# schematic.net
KiCad netlist of a schematic drawn in Altium Designer
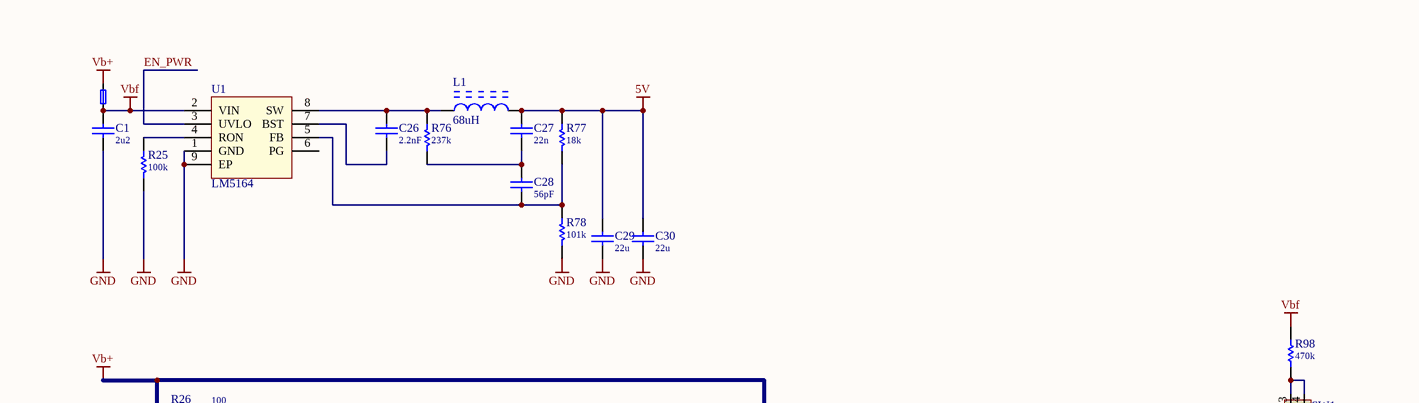
[diagram p0: schematic.SchDoc, top]
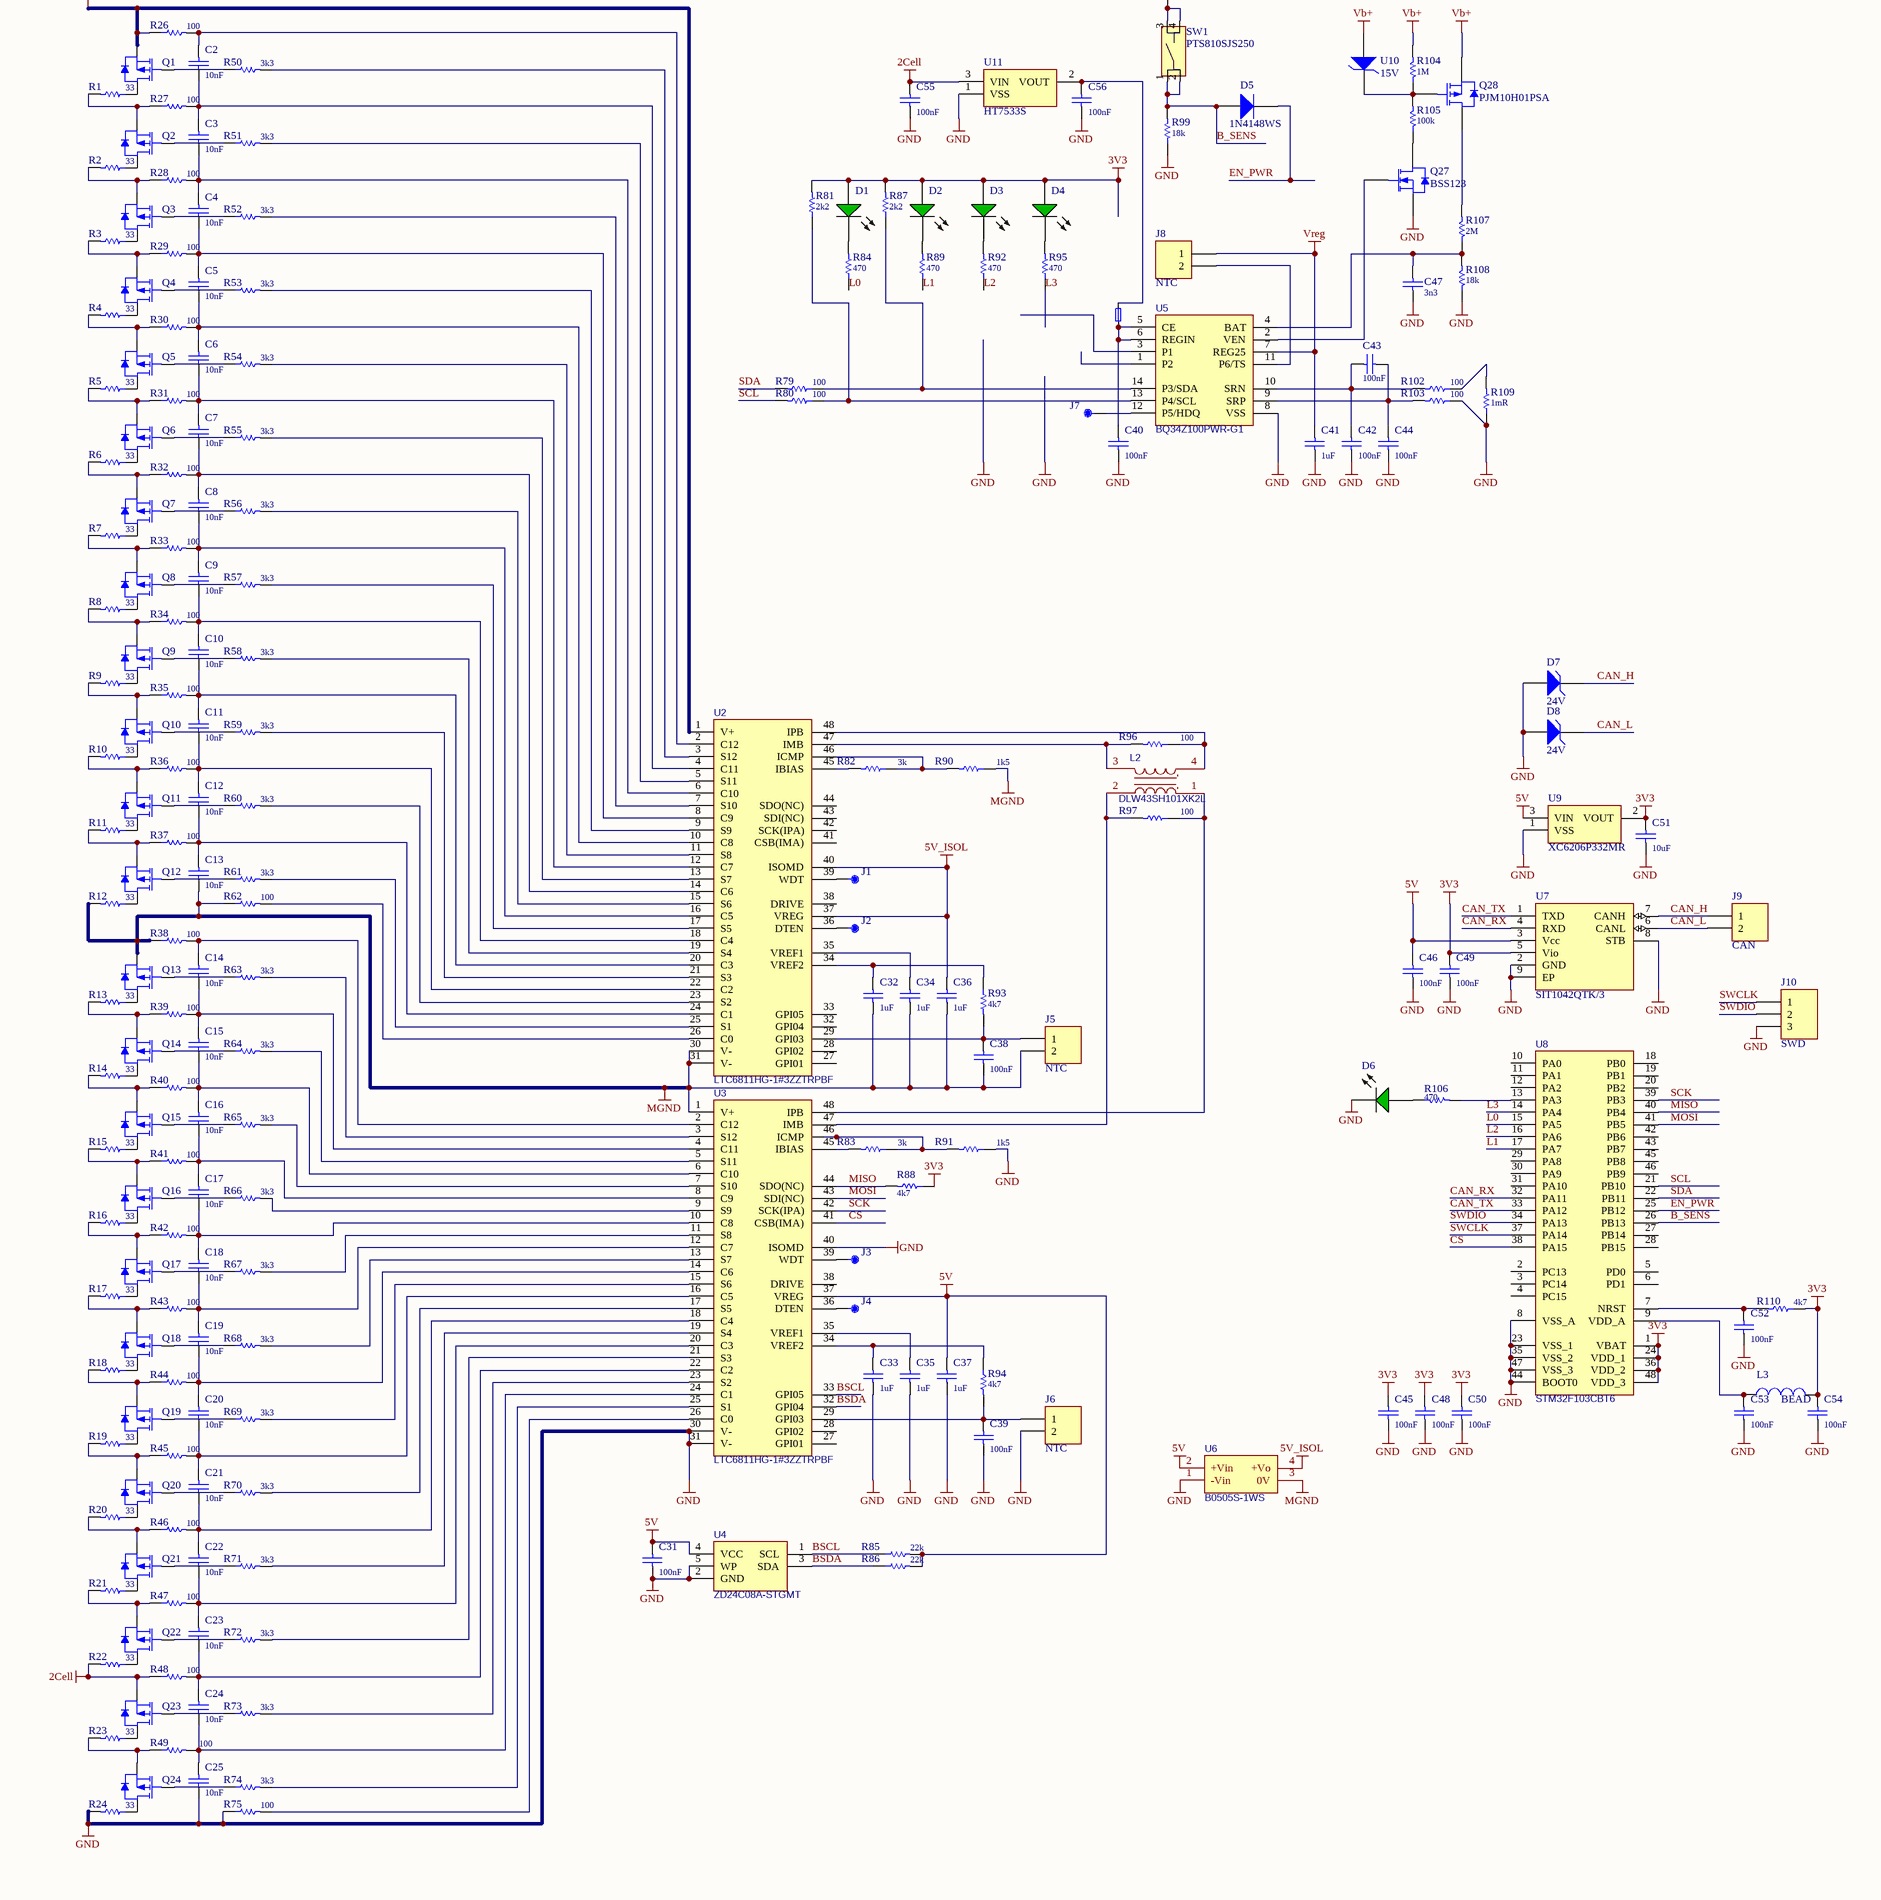
[diagram p1: schematic.SchDoc, bottom]

(export (version "E")
  (design (tool "Eeschema 10.0.6"))
  (components
    (comp (ref "C1")
      (value "2u2")
      (footprint "C1210")
      (description "2.2uF 100V 1210")
      (libsource (lib "Miscellaneous Devices") (part "CAP"))
    )
    (comp (ref "C2")
      (value "10nF")
      (footprint "C0603")
      (description "10nF 50V 0603")
      (libsource (lib "Miscellaneous Devices") (part "CAP"))
    )
    (comp (ref "C3")
      (value "10nF")
      (footprint "C0603")
      (description "10nF 50V 0603")
      (libsource (lib "Miscellaneous Devices") (part "CAP"))
    )
    (comp (ref "C4")
      (value "10nF")
      (footprint "C0603")
      (description "10nF 50V 0603")
      (libsource (lib "Miscellaneous Devices") (part "CAP"))
    )
    (comp (ref "C5")
      (value "10nF")
      (footprint "C0603")
      (description "10nF 50V 0603")
      (libsource (lib "Miscellaneous Devices") (part "CAP"))
    )
    (comp (ref "C6")
      (value "10nF")
      (footprint "C0603")
      (description "10nF 50V 0603")
      (libsource (lib "Miscellaneous Devices") (part "CAP"))
    )
    (comp (ref "C7")
      (value "10nF")
      (footprint "C0603")
      (description "10nF 50V 0603")
      (libsource (lib "Miscellaneous Devices") (part "CAP"))
    )
    (comp (ref "C8")
      (value "10nF")
      (footprint "C0603")
      (description "10nF 50V 0603")
      (libsource (lib "Miscellaneous Devices") (part "CAP"))
    )
    (comp (ref "C9")
      (value "10nF")
      (footprint "C0603")
      (description "10nF 50V 0603")
      (libsource (lib "Miscellaneous Devices") (part "CAP"))
    )
    (comp (ref "C10")
      (value "10nF")
      (footprint "C0603")
      (description "10nF 50V 0603")
      (libsource (lib "Miscellaneous Devices") (part "CAP"))
    )
    (comp (ref "C11")
      (value "10nF")
      (footprint "C0603")
      (description "10nF 50V 0603")
      (libsource (lib "Miscellaneous Devices") (part "CAP"))
    )
    (comp (ref "C12")
      (value "10nF")
      (footprint "C0603")
      (description "10nF 50V 0603")
      (libsource (lib "Miscellaneous Devices") (part "CAP"))
    )
    (comp (ref "C13")
      (value "10nF")
      (footprint "C0603")
      (description "10nF 50V 0603")
      (libsource (lib "Miscellaneous Devices") (part "CAP"))
    )
    (comp (ref "C14")
      (value "10nF")
      (footprint "C0603")
      (description "10nF 50V 0603")
      (libsource (lib "Miscellaneous Devices") (part "CAP"))
    )
    (comp (ref "C15")
      (value "10nF")
      (footprint "C0603")
      (description "10nF 50V 0603")
      (libsource (lib "Miscellaneous Devices") (part "CAP"))
    )
    (comp (ref "C16")
      (value "10nF")
      (footprint "C0603")
      (description "10nF 50V 0603")
      (libsource (lib "Miscellaneous Devices") (part "CAP"))
    )
    (comp (ref "C17")
      (value "10nF")
      (footprint "C0603")
      (description "10nF 50V 0603")
      (libsource (lib "Miscellaneous Devices") (part "CAP"))
    )
    (comp (ref "C18")
      (value "10nF")
      (footprint "C0603")
      (description "10nF 50V 0603")
      (libsource (lib "Miscellaneous Devices") (part "CAP"))
    )
    (comp (ref "C19")
      (value "10nF")
      (footprint "C0603")
      (description "10nF 50V 0603")
      (libsource (lib "Miscellaneous Devices") (part "CAP"))
    )
    (comp (ref "C20")
      (value "10nF")
      (footprint "C0603")
      (description "10nF 50V 0603")
      (libsource (lib "Miscellaneous Devices") (part "CAP"))
    )
    (comp (ref "C21")
      (value "10nF")
      (footprint "C0603")
      (description "10nF 50V 0603")
      (libsource (lib "Miscellaneous Devices") (part "CAP"))
    )
    (comp (ref "C22")
      (value "10nF")
      (footprint "C0603")
      (description "10nF 50V 0603")
      (libsource (lib "Miscellaneous Devices") (part "CAP"))
    )
    (comp (ref "C23")
      (value "10nF")
      (footprint "C0603")
      (description "10nF 50V 0603")
      (libsource (lib "Miscellaneous Devices") (part "CAP"))
    )
    (comp (ref "C24")
      (value "10nF")
      (footprint "C0603")
      (description "10nF 50V 0603")
      (libsource (lib "Miscellaneous Devices") (part "CAP"))
    )
    (comp (ref "C25")
      (value "10nF")
      (footprint "C0603")
      (description "10nF 50V 0603")
      (libsource (lib "Miscellaneous Devices") (part "CAP"))
    )
    (comp (ref "C26")
      (value "2.2nF")
      (footprint "C0603")
      (description "2.2nF 50V 0603")
      (libsource (lib "Miscellaneous Devices") (part "CAP"))
    )
    (comp (ref "C27")
      (value "22n")
      (footprint "C0603")
      (description "2.2nF 0603")
      (libsource (lib "Miscellaneous Devices") (part "CAP"))
    )
    (comp (ref "C28")
      (value "56pF")
      (footprint "C0603")
      (description "56pF 0603")
      (libsource (lib "Miscellaneous Devices") (part "CAP"))
    )
    (comp (ref "C29")
      (value "22u")
      (footprint "C1210")
      (description "22u 35V 1210")
      (libsource (lib "Miscellaneous Devices") (part "CAP"))
    )
    (comp (ref "C30")
      (value "22u")
      (footprint "C1210")
      (description "22u 35V 1210")
      (libsource (lib "Miscellaneous Devices") (part "CAP"))
    )
    (comp (ref "C31")
      (value "100nF")
      (footprint "C0402")
      (description "100nF 50V 0402")
      (libsource (lib "Miscellaneous Devices") (part "CAP"))
    )
    (comp (ref "C32")
      (value "1uF")
      (footprint "C0603")
      (description "1uF 0603")
      (libsource (lib "Miscellaneous Devices") (part "CAP"))
    )
    (comp (ref "C33")
      (value "1uF")
      (footprint "C0603")
      (description "1uF 0603")
      (libsource (lib "Miscellaneous Devices") (part "CAP"))
    )
    (comp (ref "C34")
      (value "1uF")
      (footprint "C0603")
      (description "1uF 0603")
      (libsource (lib "Miscellaneous Devices") (part "CAP"))
    )
    (comp (ref "C35")
      (value "1uF")
      (footprint "C0603")
      (description "1uF 0603")
      (libsource (lib "Miscellaneous Devices") (part "CAP"))
    )
    (comp (ref "C36")
      (value "1uF")
      (footprint "C0603")
      (description "1uF 0603")
      (libsource (lib "Miscellaneous Devices") (part "CAP"))
    )
    (comp (ref "C37")
      (value "1uF")
      (footprint "C0603")
      (description "1uF 0603")
      (libsource (lib "Miscellaneous Devices") (part "CAP"))
    )
    (comp (ref "C38")
      (value "100nF")
      (footprint "C0402")
      (description "100nF 50V 0402")
      (libsource (lib "Miscellaneous Devices") (part "CAP"))
    )
    (comp (ref "C39")
      (value "100nF")
      (footprint "C0402")
      (description "100nF 50V 0402")
      (libsource (lib "Miscellaneous Devices") (part "CAP"))
    )
    (comp (ref "C40")
      (value "100nF")
      (footprint "C0603")
      (description "100nF 50V 0603")
      (libsource (lib "Miscellaneous Devices") (part "CAP"))
    )
    (comp (ref "C41")
      (value "1uF")
      (footprint "C0603")
      (description "1uF 0603")
      (libsource (lib "Miscellaneous Devices") (part "CAP"))
    )
    (comp (ref "C42")
      (value "100nF")
      (footprint "C0603")
      (description "100nF 50V 0603")
      (libsource (lib "Miscellaneous Devices") (part "CAP"))
    )
    (comp (ref "C43")
      (value "100nF")
      (footprint "C0603")
      (description "100nF 50V 0603")
      (libsource (lib "Miscellaneous Devices") (part "CAP"))
    )
    (comp (ref "C44")
      (value "100nF")
      (footprint "C0603")
      (description "100nF 50V 0603")
      (libsource (lib "Miscellaneous Devices") (part "CAP"))
    )
    (comp (ref "C45")
      (value "100nF")
      (footprint "C0402")
      (description "100nF 50V 0402")
      (libsource (lib "Miscellaneous Devices") (part "CAP"))
    )
    (comp (ref "C46")
      (value "100nF")
      (footprint "C0402")
      (description "100nF 50V 0402")
      (libsource (lib "Miscellaneous Devices") (part "CAP"))
    )
    (comp (ref "C47")
      (value "3n3")
      (footprint "C0603")
      (description "3n3 100V 0603")
      (libsource (lib "Miscellaneous Devices") (part "CAP"))
    )
    (comp (ref "C48")
      (value "100nF")
      (footprint "C0402")
      (description "100nF 50V 0402")
      (libsource (lib "Miscellaneous Devices") (part "CAP"))
    )
    (comp (ref "C49")
      (value "100nF")
      (footprint "C0402")
      (description "100nF 50V 0402")
      (libsource (lib "Miscellaneous Devices") (part "CAP"))
    )
    (comp (ref "C50")
      (value "100nF")
      (footprint "C0402")
      (description "100nF 50V 0402")
      (libsource (lib "Miscellaneous Devices") (part "CAP"))
    )
    (comp (ref "C51")
      (value "10uF")
      (footprint "C1206")
      (description "10uf 50V 1206")
      (libsource (lib "Miscellaneous Devices") (part "CAP"))
    )
    (comp (ref "C52")
      (value "100nF")
      (footprint "C0402")
      (description "100nF 50V 0402")
      (libsource (lib "Miscellaneous Devices") (part "CAP"))
    )
    (comp (ref "C53")
      (value "100nF")
      (footprint "C0402")
      (description "100nF 50V 0402")
      (libsource (lib "Miscellaneous Devices") (part "CAP"))
    )
    (comp (ref "C54")
      (value "100nF")
      (footprint "C0402")
      (description "100nF 50V 0402")
      (libsource (lib "Miscellaneous Devices") (part "CAP"))
    )
    (comp (ref "C55")
      (value "100nF")
      (footprint "C0603")
      (description "100nF 50V 0603")
      (libsource (lib "Miscellaneous Devices") (part "CAP"))
    )
    (comp (ref "C56")
      (value "100nF")
      (footprint "C0603")
      (description "100nF 50V 0603")
      (libsource (lib "Miscellaneous Devices") (part "CAP"))
    )
    (comp (ref "D1")
      (value "GRN")
      (footprint "LED-0603-GRN")
      (description "LED 0603 GRN")
      (libsource (lib "Miscellaneous Devices") (part "LED-0603-GREEN"))
    )
    (comp (ref "D2")
      (value "GRN")
      (footprint "LED-0603-GRN")
      (description "LED 0603 GRN")
      (libsource (lib "Miscellaneous Devices") (part "LED-0603-GREEN"))
    )
    (comp (ref "D3")
      (value "GRN")
      (footprint "LED-0603-GRN")
      (description "LED 0603 GRN")
      (libsource (lib "Miscellaneous Devices") (part "LED-0603-GREEN"))
    )
    (comp (ref "D4")
      (value "GRN")
      (footprint "LED-0603-GRN")
      (description "LED 0603 GRN")
      (libsource (lib "Miscellaneous Devices") (part "LED-0603-GREEN"))
    )
    (comp (ref "D5")
      (value "1N4148WS")
      (footprint "SOD-323")
      (libsource (lib "Miscellaneous Devices") (part "US1M-13-F"))
    )
    (comp (ref "D6")
      (value "GRN")
      (footprint "LED-0603-GRN")
      (description "LED 0603 GRN")
      (libsource (lib "Miscellaneous Devices") (part "LED-0603-GREEN"))
    )
    (comp (ref "D7")
      (value "24V")
      (footprint "SOD-123FL")
      (description "P6SMB24A")
      (libsource (lib "Miscellaneous Devices") (part "SMCJ54A"))
    )
    (comp (ref "D8")
      (value "24V")
      (footprint "SOD-123FL")
      (description "P6SMB24A")
      (libsource (lib "Miscellaneous Devices") (part "SMCJ54A"))
    )
    (comp (ref "F1")
      (value "1A")
      (footprint "FUSE-1206")
      (fields (field (name "LCSC PART NUMBER") "C2924950"))
      (libsource (lib "Schlib1") (part "Fuse 1"))
    )
    (comp (ref "F2")
      (value "1A")
      (footprint "FUSE-1206")
      (fields (field (name "LCSC PART NUMBER") "C2924950"))
      (libsource (lib "Schlib1") (part "Fuse 1"))
    )
    (comp (ref "J1")
      (value "~")
      (footprint "TP30_SMD")
      (libsource (lib "Miscellaneous Connectors") (part "TP_Dup1"))
    )
    (comp (ref "J2")
      (value "~")
      (footprint "TP30_SMD")
      (libsource (lib "Miscellaneous Connectors") (part "TP_Dup1"))
    )
    (comp (ref "J3")
      (value "~")
      (footprint "TP30_SMD")
      (libsource (lib "Miscellaneous Connectors") (part "TP_Dup1"))
    )
    (comp (ref "J4")
      (value "~")
      (footprint "TP30_SMD")
      (libsource (lib "Miscellaneous Connectors") (part "TP_Dup1"))
    )
    (comp (ref "J5") (value "NTC") (footprint "HDR-1X2") (libsource (lib "Schlib1") (part "Header 2")))
    (comp (ref "J6") (value "NTC") (footprint "HDR-1X2") (libsource (lib "Schlib1") (part "Header 2")))
    (comp (ref "J7")
      (value "~")
      (footprint "TP30_SMD")
      (libsource (lib "Miscellaneous Connectors") (part "TP_Dup1"))
    )
    (comp (ref "J8") (value "NTC") (footprint "HDR-1X2") (libsource (lib "") (part "Header 2_1")))
    (comp (ref "J9") (value "CAN") (footprint "HDR-1X2") (libsource (lib "Schlib1") (part "Header 2")))
    (comp (ref "J10")
      (value "SWD")
      (footprint "HDR-1X3")
      (libsource (lib "Miscellaneous Devices") (part "Header 3"))
    )
    (comp (ref "L1")
      (value "68uH")
      (footprint "L0605-POWER")
      (description "PSPMAA0605H-680M-IGF")
      (libsource (lib "Miscellaneous Devices") (part "SRN3015-100M"))
    )
    (comp (ref "L2")
      (value "DLW43SH101XK2L")
      (footprint "FILTER-SMD_4P-L4.5-W3.2-BL")
      (libsource (lib "altium-import") (part "root_2_DLW43SH101XK2L_"))
    )
    (comp (ref "L3")
      (value "BEAD")
      (footprint "L0402")
      (description "BEAD 0402")
      (libsource (lib "Miscellaneous Devices") (part "BLM18AG601SN1D"))
    )
    (comp (ref "Q1")
      (value "BSS308PE-VB")
      (footprint "SOT-23")
      (libsource (lib "Miscellaneous Devices") (part "2N7002"))
    )
    (comp (ref "Q2")
      (value "BSS308PE-VB")
      (footprint "SOT-23")
      (libsource (lib "Miscellaneous Devices") (part "2N7002"))
    )
    (comp (ref "Q3")
      (value "BSS308PE-VB")
      (footprint "SOT-23")
      (libsource (lib "Miscellaneous Devices") (part "2N7002"))
    )
    (comp (ref "Q4")
      (value "BSS308PE-VB")
      (footprint "SOT-23")
      (libsource (lib "Miscellaneous Devices") (part "2N7002"))
    )
    (comp (ref "Q5")
      (value "BSS308PE-VB")
      (footprint "SOT-23")
      (libsource (lib "Miscellaneous Devices") (part "2N7002"))
    )
    (comp (ref "Q6")
      (value "BSS308PE-VB")
      (footprint "SOT-23")
      (libsource (lib "Miscellaneous Devices") (part "2N7002"))
    )
    (comp (ref "Q7")
      (value "BSS308PE-VB")
      (footprint "SOT-23")
      (libsource (lib "Miscellaneous Devices") (part "2N7002"))
    )
    (comp (ref "Q8")
      (value "BSS308PE-VB")
      (footprint "SOT-23")
      (libsource (lib "Miscellaneous Devices") (part "2N7002"))
    )
    (comp (ref "Q9")
      (value "BSS308PE-VB")
      (footprint "SOT-23")
      (libsource (lib "Miscellaneous Devices") (part "2N7002"))
    )
    (comp (ref "Q10")
      (value "BSS308PE-VB")
      (footprint "SOT-23")
      (libsource (lib "Miscellaneous Devices") (part "2N7002"))
    )
    (comp (ref "Q11")
      (value "BSS308PE-VB")
      (footprint "SOT-23")
      (libsource (lib "Miscellaneous Devices") (part "2N7002"))
    )
    (comp (ref "Q12")
      (value "BSS308PE-VB")
      (footprint "SOT-23")
      (libsource (lib "Miscellaneous Devices") (part "2N7002"))
    )
    (comp (ref "Q13")
      (value "BSS308PE-VB")
      (footprint "SOT-23")
      (libsource (lib "Miscellaneous Devices") (part "2N7002"))
    )
    (comp (ref "Q14")
      (value "BSS308PE-VB")
      (footprint "SOT-23")
      (libsource (lib "Miscellaneous Devices") (part "2N7002"))
    )
    (comp (ref "Q15")
      (value "BSS308PE-VB")
      (footprint "SOT-23")
      (libsource (lib "Miscellaneous Devices") (part "2N7002"))
    )
    (comp (ref "Q16")
      (value "BSS308PE-VB")
      (footprint "SOT-23")
      (libsource (lib "Miscellaneous Devices") (part "2N7002"))
    )
    (comp (ref "Q17")
      (value "BSS308PE-VB")
      (footprint "SOT-23")
      (libsource (lib "Miscellaneous Devices") (part "2N7002"))
    )
    (comp (ref "Q18")
      (value "BSS308PE-VB")
      (footprint "SOT-23")
      (libsource (lib "Miscellaneous Devices") (part "2N7002"))
    )
    (comp (ref "Q19")
      (value "BSS308PE-VB")
      (footprint "SOT-23")
      (libsource (lib "Miscellaneous Devices") (part "2N7002"))
    )
    (comp (ref "Q20")
      (value "BSS308PE-VB")
      (footprint "SOT-23")
      (libsource (lib "Miscellaneous Devices") (part "2N7002"))
    )
    (comp (ref "Q21")
      (value "BSS308PE-VB")
      (footprint "SOT-23")
      (libsource (lib "Miscellaneous Devices") (part "2N7002"))
    )
    (comp (ref "Q22")
      (value "BSS308PE-VB")
      (footprint "SOT-23")
      (libsource (lib "Miscellaneous Devices") (part "2N7002"))
    )
    (comp (ref "Q23")
      (value "BSS308PE-VB")
      (footprint "SOT-23")
      (libsource (lib "Miscellaneous Devices") (part "2N7002"))
    )
    (comp (ref "Q24")
      (value "BSS308PE-VB")
      (footprint "SOT-23")
      (libsource (lib "Miscellaneous Devices") (part "2N7002"))
    )
    (comp (ref "Q27") (value "BSS123") (footprint "SOT-23") (libsource (lib "") (part "2N7002_1")))
    (comp (ref "Q28") (value "PJM10H01PSA") (footprint "SOT-23") (libsource (lib "Schlib1") (part "2N7002")))
    (comp (ref "R1")
      (value "33")
      (footprint "R2512")
      (description "33R 2512")
      (libsource (lib "Miscellaneous Devices") (part "RES"))
    )
    (comp (ref "R2")
      (value "33")
      (footprint "R2512")
      (description "33R 2512")
      (libsource (lib "Miscellaneous Devices") (part "RES"))
    )
    (comp (ref "R3")
      (value "33")
      (footprint "R2512")
      (description "33R 2512")
      (libsource (lib "Miscellaneous Devices") (part "RES"))
    )
    (comp (ref "R4")
      (value "33")
      (footprint "R2512")
      (description "33R 2512")
      (libsource (lib "Miscellaneous Devices") (part "RES"))
    )
    (comp (ref "R5")
      (value "33")
      (footprint "R2512")
      (description "33R 2512")
      (libsource (lib "Miscellaneous Devices") (part "RES"))
    )
    (comp (ref "R6")
      (value "33")
      (footprint "R2512")
      (description "33R 2512")
      (libsource (lib "Miscellaneous Devices") (part "RES"))
    )
    (comp (ref "R7")
      (value "33")
      (footprint "R2512")
      (description "33R 2512")
      (libsource (lib "Miscellaneous Devices") (part "RES"))
    )
    (comp (ref "R8")
      (value "33")
      (footprint "R2512")
      (description "33R 2512")
      (libsource (lib "Miscellaneous Devices") (part "RES"))
    )
    (comp (ref "R9")
      (value "33")
      (footprint "R2512")
      (description "33R 2512")
      (libsource (lib "Miscellaneous Devices") (part "RES"))
    )
    (comp (ref "R10")
      (value "33")
      (footprint "R2512")
      (description "33R 2512")
      (libsource (lib "Miscellaneous Devices") (part "RES"))
    )
    (comp (ref "R11")
      (value "33")
      (footprint "R2512")
      (description "33R 2512")
      (libsource (lib "Miscellaneous Devices") (part "RES"))
    )
    (comp (ref "R12")
      (value "33")
      (footprint "R2512")
      (description "33R 2512")
      (libsource (lib "Miscellaneous Devices") (part "RES"))
    )
    (comp (ref "R13")
      (value "33")
      (footprint "R2512")
      (description "33R 2512")
      (libsource (lib "Miscellaneous Devices") (part "RES"))
    )
    (comp (ref "R14")
      (value "33")
      (footprint "R2512")
      (description "33R 2512")
      (libsource (lib "Miscellaneous Devices") (part "RES"))
    )
    (comp (ref "R15")
      (value "33")
      (footprint "R2512")
      (description "33R 2512")
      (libsource (lib "Miscellaneous Devices") (part "RES"))
    )
    (comp (ref "R16")
      (value "33")
      (footprint "R2512")
      (description "33R 2512")
      (libsource (lib "Miscellaneous Devices") (part "RES"))
    )
    (comp (ref "R17")
      (value "33")
      (footprint "R2512")
      (description "33R 2512")
      (libsource (lib "Miscellaneous Devices") (part "RES"))
    )
    (comp (ref "R18")
      (value "33")
      (footprint "R2512")
      (description "33R 2512")
      (libsource (lib "Miscellaneous Devices") (part "RES"))
    )
    (comp (ref "R19")
      (value "33")
      (footprint "R2512")
      (description "33R 2512")
      (libsource (lib "Miscellaneous Devices") (part "RES"))
    )
    (comp (ref "R20")
      (value "33")
      (footprint "R2512")
      (description "33R 2512")
      (libsource (lib "Miscellaneous Devices") (part "RES"))
    )
    (comp (ref "R21")
      (value "33")
      (footprint "R2512")
      (description "33R 2512")
      (libsource (lib "Miscellaneous Devices") (part "RES"))
    )
    (comp (ref "R22")
      (value "33")
      (footprint "R2512")
      (description "33R 2512")
      (libsource (lib "Miscellaneous Devices") (part "RES"))
    )
    (comp (ref "R23")
      (value "33")
      (footprint "R2512")
      (description "33R 2512")
      (libsource (lib "Miscellaneous Devices") (part "RES"))
    )
    (comp (ref "R24")
      (value "33")
      (footprint "R2512")
      (description "33R 2512")
      (libsource (lib "Miscellaneous Devices") (part "RES"))
    )
    (comp (ref "R25")
      (value "100k")
      (footprint "R0603")
      (description "100k 0603")
      (libsource (lib "Miscellaneous Devices") (part "RES"))
    )
    (comp (ref "R26")
      (value "100")
      (footprint "R0603")
      (description "100R 0603")
      (libsource (lib "Miscellaneous Devices") (part "RES"))
    )
    (comp (ref "R27")
      (value "100")
      (footprint "R0603")
      (description "100R 0603")
      (libsource (lib "Miscellaneous Devices") (part "RES"))
    )
    (comp (ref "R28")
      (value "100")
      (footprint "R0603")
      (description "100R 0603")
      (libsource (lib "Miscellaneous Devices") (part "RES"))
    )
    (comp (ref "R29")
      (value "100")
      (footprint "R0603")
      (description "100R 0603")
      (libsource (lib "Miscellaneous Devices") (part "RES"))
    )
    (comp (ref "R30")
      (value "100")
      (footprint "R0603")
      (description "100R 0603")
      (libsource (lib "Miscellaneous Devices") (part "RES"))
    )
    (comp (ref "R31")
      (value "100")
      (footprint "R0603")
      (description "100R 0603")
      (libsource (lib "Miscellaneous Devices") (part "RES"))
    )
    (comp (ref "R32")
      (value "100")
      (footprint "R0603")
      (description "100R 0603")
      (libsource (lib "Miscellaneous Devices") (part "RES"))
    )
    (comp (ref "R33")
      (value "100")
      (footprint "R0603")
      (description "100R 0603")
      (libsource (lib "Miscellaneous Devices") (part "RES"))
    )
    (comp (ref "R34")
      (value "100")
      (footprint "R0603")
      (description "100R 0603")
      (libsource (lib "Miscellaneous Devices") (part "RES"))
    )
    (comp (ref "R35")
      (value "100")
      (footprint "R0603")
      (description "100R 0603")
      (libsource (lib "Miscellaneous Devices") (part "RES"))
    )
    (comp (ref "R36")
      (value "100")
      (footprint "R0603")
      (description "100R 0603")
      (libsource (lib "Miscellaneous Devices") (part "RES"))
    )
    (comp (ref "R37")
      (value "100")
      (footprint "R0603")
      (description "100R 0603")
      (libsource (lib "Miscellaneous Devices") (part "RES"))
    )
    (comp (ref "R38")
      (value "100")
      (footprint "R0603")
      (description "100R 0603")
      (libsource (lib "Miscellaneous Devices") (part "RES"))
    )
    (comp (ref "R39")
      (value "100")
      (footprint "R0603")
      (description "100R 0603")
      (libsource (lib "Miscellaneous Devices") (part "RES"))
    )
    (comp (ref "R40")
      (value "100")
      (footprint "R0603")
      (description "100R 0603")
      (libsource (lib "Miscellaneous Devices") (part "RES"))
    )
    (comp (ref "R41")
      (value "100")
      (footprint "R0603")
      (description "100R 0603")
      (libsource (lib "Miscellaneous Devices") (part "RES"))
    )
    (comp (ref "R42")
      (value "100")
      (footprint "R0603")
      (description "100R 0603")
      (libsource (lib "Miscellaneous Devices") (part "RES"))
    )
    (comp (ref "R43")
      (value "100")
      (footprint "R0603")
      (description "100R 0603")
      (libsource (lib "Miscellaneous Devices") (part "RES"))
    )
    (comp (ref "R44")
      (value "100")
      (footprint "R0603")
      (description "100R 0603")
      (libsource (lib "Miscellaneous Devices") (part "RES"))
    )
    (comp (ref "R45")
      (value "100")
      (footprint "R0603")
      (description "100R 0603")
      (libsource (lib "Miscellaneous Devices") (part "RES"))
    )
    (comp (ref "R46")
      (value "100")
      (footprint "R0603")
      (description "100R 0603")
      (libsource (lib "Miscellaneous Devices") (part "RES"))
    )
    (comp (ref "R47")
      (value "100")
      (footprint "R0603")
      (description "100R 0603")
      (libsource (lib "Miscellaneous Devices") (part "RES"))
    )
    (comp (ref "R48")
      (value "100")
      (footprint "R0603")
      (description "100R 0603")
      (libsource (lib "Miscellaneous Devices") (part "RES"))
    )
    (comp (ref "R49")
      (value "100")
      (footprint "R0603")
      (description "100R 0603")
      (libsource (lib "Miscellaneous Devices") (part "RES"))
    )
    (comp (ref "R50")
      (value "3k3")
      (footprint "R0603")
      (description "3k3 0603")
      (libsource (lib "Miscellaneous Devices") (part "RES"))
    )
    (comp (ref "R51")
      (value "3k3")
      (footprint "R0603")
      (description "3k3 0603")
      (libsource (lib "Miscellaneous Devices") (part "RES"))
    )
    (comp (ref "R52")
      (value "3k3")
      (footprint "R0603")
      (description "3k3 0603")
      (libsource (lib "Miscellaneous Devices") (part "RES"))
    )
    (comp (ref "R53")
      (value "3k3")
      (footprint "R0603")
      (description "3k3 0603")
      (libsource (lib "Miscellaneous Devices") (part "RES"))
    )
    (comp (ref "R54")
      (value "3k3")
      (footprint "R0603")
      (description "3k3 0603")
      (libsource (lib "Miscellaneous Devices") (part "RES"))
    )
    (comp (ref "R55")
      (value "3k3")
      (footprint "R0603")
      (description "3k3 0603")
      (libsource (lib "Miscellaneous Devices") (part "RES"))
    )
    (comp (ref "R56")
      (value "3k3")
      (footprint "R0603")
      (description "3k3 0603")
      (libsource (lib "Miscellaneous Devices") (part "RES"))
    )
    (comp (ref "R57")
      (value "3k3")
      (footprint "R0603")
      (description "3k3 0603")
      (libsource (lib "Miscellaneous Devices") (part "RES"))
    )
    (comp (ref "R58")
      (value "3k3")
      (footprint "R0603")
      (description "3k3 0603")
      (libsource (lib "Miscellaneous Devices") (part "RES"))
    )
    (comp (ref "R59")
      (value "3k3")
      (footprint "R0603")
      (description "3k3 0603")
      (libsource (lib "Miscellaneous Devices") (part "RES"))
    )
    (comp (ref "R60")
      (value "3k3")
      (footprint "R0603")
      (description "3k3 0603")
      (libsource (lib "Miscellaneous Devices") (part "RES"))
    )
    (comp (ref "R61")
      (value "3k3")
      (footprint "R0603")
      (description "3k3 0603")
      (libsource (lib "Miscellaneous Devices") (part "RES"))
    )
    (comp (ref "R62")
      (value "100")
      (footprint "R0603")
      (description "100R 0603")
      (libsource (lib "Miscellaneous Devices") (part "RES"))
    )
    (comp (ref "R63")
      (value "3k3")
      (footprint "R0603")
      (description "3k3 0603")
      (libsource (lib "Miscellaneous Devices") (part "RES"))
    )
    (comp (ref "R64")
      (value "3k3")
      (footprint "R0603")
      (description "3k3 0603")
      (libsource (lib "Miscellaneous Devices") (part "RES"))
    )
    (comp (ref "R65")
      (value "3k3")
      (footprint "R0603")
      (description "3k3 0603")
      (libsource (lib "Miscellaneous Devices") (part "RES"))
    )
    (comp (ref "R66")
      (value "3k3")
      (footprint "R0603")
      (description "3k3 0603")
      (libsource (lib "Miscellaneous Devices") (part "RES"))
    )
    (comp (ref "R67")
      (value "3k3")
      (footprint "R0603")
      (description "3k3 0603")
      (libsource (lib "Miscellaneous Devices") (part "RES"))
    )
    (comp (ref "R68")
      (value "3k3")
      (footprint "R0603")
      (description "3k3 0603")
      (libsource (lib "Miscellaneous Devices") (part "RES"))
    )
    (comp (ref "R69")
      (value "3k3")
      (footprint "R0603")
      (description "3k3 0603")
      (libsource (lib "Miscellaneous Devices") (part "RES"))
    )
    (comp (ref "R70")
      (value "3k3")
      (footprint "R0603")
      (description "3k3 0603")
      (libsource (lib "Miscellaneous Devices") (part "RES"))
    )
    (comp (ref "R71")
      (value "3k3")
      (footprint "R0603")
      (description "3k3 0603")
      (libsource (lib "Miscellaneous Devices") (part "RES"))
    )
    (comp (ref "R72")
      (value "3k3")
      (footprint "R0603")
      (description "3k3 0603")
      (libsource (lib "Miscellaneous Devices") (part "RES"))
    )
    (comp (ref "R73")
      (value "3k3")
      (footprint "R0603")
      (description "3k3 0603")
      (libsource (lib "Miscellaneous Devices") (part "RES"))
    )
    (comp (ref "R74")
      (value "3k3")
      (footprint "R0603")
      (description "3k3 0603")
      (libsource (lib "Miscellaneous Devices") (part "RES"))
    )
    (comp (ref "R75")
      (value "100")
      (footprint "R0603")
      (description "100R 0603")
      (libsource (lib "Miscellaneous Devices") (part "RES"))
    )
    (comp (ref "R76")
      (value "237k")
      (footprint "R0603")
      (description "237k 0603")
      (libsource (lib "Miscellaneous Devices") (part "RES"))
    )
    (comp (ref "R77")
      (value "18k")
      (footprint "R0603")
      (description "18k 1% 0603")
      (libsource (lib "Miscellaneous Devices") (part "RES"))
    )
    (comp (ref "R78")
      (value "101k")
      (footprint "R0603")
      (description "101k 0603")
      (libsource (lib "Miscellaneous Devices") (part "RES"))
    )
    (comp (ref "R79")
      (value "100")
      (footprint "R0603")
      (description "100R 0603")
      (libsource (lib "Miscellaneous Devices") (part "RES"))
    )
    (comp (ref "R80")
      (value "100")
      (footprint "R0603")
      (description "100R 0603")
      (libsource (lib "Miscellaneous Devices") (part "RES"))
    )
    (comp (ref "R81")
      (value "2k2")
      (footprint "R0603")
      (description "2.2k 0603")
      (libsource (lib "Miscellaneous Devices") (part "RES"))
    )
    (comp (ref "R82")
      (value "3k")
      (footprint "R0603")
      (description "3k 0603")
      (libsource (lib "Miscellaneous Devices") (part "RES"))
    )
    (comp (ref "R83")
      (value "3k")
      (footprint "R0603")
      (description "3k 0603")
      (libsource (lib "Miscellaneous Devices") (part "RES"))
    )
    (comp (ref "R84")
      (value "470")
      (footprint "R0603")
      (description "470R 0603")
      (libsource (lib "Miscellaneous Devices") (part "RES"))
    )
    (comp (ref "R85")
      (value "22k")
      (footprint "R0402")
      (description "22k 0402")
      (libsource (lib "Miscellaneous Devices") (part "RES"))
    )
    (comp (ref "R86")
      (value "22k")
      (footprint "R0402")
      (description "22k 0402")
      (libsource (lib "Miscellaneous Devices") (part "RES"))
    )
    (comp (ref "R87")
      (value "2k2")
      (footprint "R0603")
      (description "2.2k 0603")
      (libsource (lib "Miscellaneous Devices") (part "RES"))
    )
    (comp (ref "R88")
      (value "4k7")
      (footprint "R0402")
      (description "4.7k 0603")
      (libsource (lib "Miscellaneous Devices") (part "RES"))
    )
    (comp (ref "R89")
      (value "470")
      (footprint "R0603")
      (description "470R 0603")
      (libsource (lib "Miscellaneous Devices") (part "RES"))
    )
    (comp (ref "R90")
      (value "1k5")
      (footprint "R0603")
      (description "1.5k 0603")
      (libsource (lib "Miscellaneous Devices") (part "RES"))
    )
    (comp (ref "R91")
      (value "1k5")
      (footprint "R0603")
      (description "1.5k 0603")
      (libsource (lib "Miscellaneous Devices") (part "RES"))
    )
    (comp (ref "R92")
      (value "470")
      (footprint "R0603")
      (description "470R 0603")
      (libsource (lib "Miscellaneous Devices") (part "RES"))
    )
    (comp (ref "R93")
      (value "4k7")
      (footprint "R0603")
      (description "4.7k 0603")
      (libsource (lib "Miscellaneous Devices") (part "RES"))
    )
    (comp (ref "R94")
      (value "4k7")
      (footprint "R0603")
      (description "4.7k 0603")
      (libsource (lib "Miscellaneous Devices") (part "RES"))
    )
    (comp (ref "R95")
      (value "470")
      (footprint "R0603")
      (description "470R 0603")
      (libsource (lib "Miscellaneous Devices") (part "RES"))
    )
    (comp (ref "R96")
      (value "100")
      (footprint "R0603")
      (description "100R 0603")
      (libsource (lib "Miscellaneous Devices") (part "RES"))
    )
    (comp (ref "R97")
      (value "100")
      (footprint "R0603")
      (description "100R 0603")
      (libsource (lib "Miscellaneous Devices") (part "RES"))
    )
    (comp (ref "R98")
      (value "470k")
      (footprint "R1206")
      (description "470k 1206")
      (libsource (lib "Miscellaneous Devices") (part "RES"))
    )
    (comp (ref "R99")
      (value "18k")
      (footprint "R0603")
      (description "18k 0603")
      (libsource (lib "Miscellaneous Devices") (part "RES"))
    )
    (comp (ref "R102")
      (value "100")
      (footprint "R0603")
      (description "100R 0603")
      (libsource (lib "Miscellaneous Devices") (part "RES"))
    )
    (comp (ref "R103")
      (value "100")
      (footprint "R0603")
      (description "100R 0603")
      (libsource (lib "Miscellaneous Devices") (part "RES"))
    )
    (comp (ref "R104")
      (value "1M")
      (footprint "R1206")
      (description "1M 1206")
      (libsource (lib "Miscellaneous Devices") (part "RES"))
    )
    (comp (ref "R105")
      (value "100k")
      (footprint "R1206")
      (description "100k 1206")
      (libsource (lib "Miscellaneous Devices") (part "RES"))
    )
    (comp (ref "R106")
      (value "470")
      (footprint "R0603")
      (description "470 0603")
      (libsource (lib "Miscellaneous Devices") (part "RES"))
    )
    (comp (ref "R107")
      (value "2M")
      (footprint "R1206")
      (description "2M 1206")
      (libsource (lib "Miscellaneous Devices") (part "RES"))
    )
    (comp (ref "R108")
      (value "18k")
      (footprint "R0603")
      (description "18k 0603")
      (libsource (lib "Miscellaneous Devices") (part "RES"))
    )
    (comp (ref "R109")
      (value "1mR")
      (footprint "R5930_SHUNT")
      (description "HolRS5930-7W-1mR-1%")
      (libsource (lib "Miscellaneous Devices") (part "RES"))
    )
    (comp (ref "R110")
      (value "4k7")
      (footprint "R0402")
      (description "4k7 0402")
      (libsource (lib "Miscellaneous Devices") (part "RES"))
    )
    (comp (ref "SW1")
      (value "PTS810SJS250")
      (footprint "BTN_PTS810")
      (libsource (lib "Miscellaneous Devices") (part "Component_1"))
    )
    (comp (ref "U1") (value "LM5164") (footprint "PowerSOIC-8") (libsource (lib "Schlib2") (part "LM5164")))
    (comp (ref "U2")
      (value "LTC6811HG-1#3ZZTRPBF")
      (footprint "SSOP-48_L12.8-W5.3-P0.50-LS7.8-BL")
      (libsource (lib "Schlib1") (part "LTC6811HG-1#3ZZTRPBF"))
    )
    (comp (ref "U3")
      (value "LTC6811HG-1#3ZZTRPBF")
      (footprint "SSOP-48_L12.8-W5.3-P0.50-LS7.8-BL")
      (libsource (lib "Schlib1") (part "LTC6811HG-1#3ZZTRPBF"))
    )
    (comp (ref "U4")
      (value "ZD24C08A-STGMT")
      (footprint "SOT-23-5")
      (libsource (lib "Schlib1") (part "ZD24C08A-STGMT"))
    )
    (comp (ref "U5")
      (value "BQ34Z100PWR-G1")
      (footprint "TSSOP-14_L5.0-W4.4-P0.65-LS6.4-BL")
      (libsource (lib "Schlib1") (part "BQ34Z100PWR-G1"))
    )
    (comp (ref "U6")
      (value "B0505S-1WS")
      (footprint "B0505S-1WS")
      (libsource (lib "Schlib1") (part "B0505S-1WR3_C512048"))
    )
    (comp (ref "U7")
      (value "SIT1042QTK/3")
      (footprint "DFN8_3X3_P065")
      (description "IC INTERFACE CAN")
      (libsource (lib "Miscellaneous Devices") (part "LTC2875"))
    )
    (comp (ref "U8")
      (value "STM32F103CBT6")
      (footprint "LQFP-48")
      (libsource (lib "Schlib1") (part "STM32F103CBT6"))
    )
    (comp (ref "U9")
      (value "XC6206P332MR")
      (footprint "SOT-23")
      (libsource (lib "Schlib1") (part "Component_4_1"))
    )
    (comp (ref "U10")
      (value "15V")
      (footprint "SOD-323")
      (description "BZT52C15S")
      (libsource (lib "Miscellaneous Devices") (part "NCP51460SN33T1G"))
    )
    (comp (ref "U11")
      (value "HT7533S")
      (footprint "SOT-23")
      (libsource (lib "Schlib1") (part "Component_4_1"))
    )
  )
  (nets
    (net (code "1") (name "/BSCL") (class "Default")
      (node (ref "R85") (pin "1") (pinfunction "1_1") (pintype "passive"))
      (node (ref "U3") (pin "33") (pinfunction "GPI05_33") (pintype "passive"))
      (node (ref "U4") (pin "1") (pinfunction "SCL_1") (pintype "passive"))
    )
    (net (code "2") (name "/BSDA") (class "Default")
      (node (ref "R86") (pin "1") (pinfunction "1_1") (pintype "passive"))
      (node (ref "U3") (pin "32") (pinfunction "GPI04_32") (pintype "passive"))
      (node (ref "U4") (pin "3") (pinfunction "SDA_3") (pintype "passive"))
    )
    (net (code "3") (name "/B_SENS") (class "Default")
      (node (ref "D5") (pin "1") (pinfunction "A_1") (pintype "passive"))
      (node (ref "R99") (pin "2") (pinfunction "2_2") (pintype "passive"))
      (node (ref "SW1") (pin "1") (pinfunction "1_1") (pintype "passive"))
      (node (ref "SW1") (pin "2") (pinfunction "2_2") (pintype "passive"))
      (node (ref "U8") (pin "26") (pinfunction "PB13_26") (pintype "passive"))
    )
    (net (code "4") (name "/CAN_H") (class "Default")
      (node (ref "D7") (pin "2") (pinfunction "K_2") (pintype "passive"))
      (node (ref "J9") (pin "1") (pinfunction "1_1") (pintype "passive"))
      (node (ref "U7") (pin "7") (pinfunction "CANH_7") (pintype "bidirectional"))
    )
    (net (code "5") (name "/CAN_L") (class "Default")
      (node (ref "D8") (pin "2") (pinfunction "K_2") (pintype "passive"))
      (node (ref "J9") (pin "2") (pinfunction "2_2") (pintype "passive"))
      (node (ref "U7") (pin "6") (pinfunction "CANL_6") (pintype "bidirectional"))
    )
    (net (code "6") (name "/CAN_RX") (class "Default")
      (node (ref "U7") (pin "4") (pinfunction "RXD_4") (pintype "passive"))
      (node (ref "U8") (pin "32") (pinfunction "PA11_32") (pintype "passive"))
    )
    (net (code "7") (name "/CAN_TX") (class "Default")
      (node (ref "U7") (pin "1") (pinfunction "TXD_1") (pintype "passive"))
      (node (ref "U8") (pin "33") (pinfunction "PA12_33") (pintype "passive"))
    )
    (net (code "8") (name "/CS") (class "Default")
      (node (ref "U3") (pin "41") (pinfunction "CSB(IMA)_41") (pintype "passive"))
      (node (ref "U8") (pin "38") (pinfunction "PA15_38") (pintype "passive"))
    )
    (net (code "9") (name "/EN_PWR") (class "Default")
      (node (ref "D5") (pin "2") (pinfunction "K_2") (pintype "passive"))
      (node (ref "U1") (pin "3") (pinfunction "UVLO_3") (pintype "passive"))
      (node (ref "U8") (pin "25") (pinfunction "PB12_25") (pintype "passive"))
    )
    (net (code "10") (name "/L0") (class "Default")
      (node (ref "R84") (pin "1") (pinfunction "1_1") (pintype "passive"))
      (node (ref "U8") (pin "15") (pinfunction "PA5_15") (pintype "passive"))
    )
    (net (code "11") (name "/L1") (class "Default")
      (node (ref "R89") (pin "1") (pinfunction "1_1") (pintype "passive"))
      (node (ref "U8") (pin "17") (pinfunction "PA7_17") (pintype "passive"))
    )
    (net (code "12") (name "/L2") (class "Default")
      (node (ref "R92") (pin "1") (pinfunction "1_1") (pintype "passive"))
      (node (ref "U8") (pin "16") (pinfunction "PA6_16") (pintype "passive"))
    )
    (net (code "13") (name "/L3") (class "Default")
      (node (ref "R95") (pin "1") (pinfunction "1_1") (pintype "passive"))
      (node (ref "U8") (pin "14") (pinfunction "PA4_14") (pintype "passive"))
    )
    (net (code "14") (name "/MISO") (class "Default")
      (node (ref "R88") (pin "2") (pinfunction "2_2") (pintype "passive"))
      (node (ref "U3") (pin "44") (pinfunction "SDO(NC)_44") (pintype "passive"))
      (node (ref "U8") (pin "40") (pinfunction "PB4_40") (pintype "passive"))
    )
    (net (code "15") (name "/MOSI") (class "Default")
      (node (ref "U3") (pin "43") (pinfunction "SDI(NC)_43") (pintype "passive"))
      (node (ref "U8") (pin "41") (pinfunction "PB5_41") (pintype "passive"))
    )
    (net (code "16") (name "/SCK") (class "Default")
      (node (ref "U3") (pin "42") (pinfunction "SCK(IPA)_42") (pintype "passive"))
      (node (ref "U8") (pin "39") (pinfunction "PB3_39") (pintype "passive"))
    )
    (net (code "17") (name "/SCL") (class "Default")
      (node (ref "R80") (pin "2") (pinfunction "2_2") (pintype "passive"))
      (node (ref "U8") (pin "21") (pinfunction "PB10_21") (pintype "passive"))
    )
    (net (code "18") (name "/SDA") (class "Default")
      (node (ref "R79") (pin "2") (pinfunction "2_2") (pintype "passive"))
      (node (ref "U8") (pin "22") (pinfunction "PB11_22") (pintype "passive"))
    )
    (net (code "19") (name "/SWCLK") (class "Default")
      (node (ref "J10") (pin "1") (pinfunction "1_1") (pintype "passive"))
      (node (ref "U8") (pin "37") (pinfunction "PA14_37") (pintype "passive"))
    )
    (net (code "20") (name "/SWDIO") (class "Default")
      (node (ref "J10") (pin "2") (pinfunction "2_2") (pintype "passive"))
      (node (ref "U8") (pin "34") (pinfunction "PA13_34") (pintype "passive"))
    )
    (net (code "21") (name "2Cell") (class "Default")
      (node (ref "C55") (pin "2") (pinfunction "2_2") (pintype "passive"))
      (node (ref "Q23") (pin "2") (pinfunction "SOURCE_2") (pintype "passive"))
      (node (ref "R22") (pin "2") (pinfunction "2_2") (pintype "passive"))
      (node (ref "R48") (pin "1") (pinfunction "1_1") (pintype "passive"))
      (node (ref "U11") (pin "3") (pinfunction "VIN_3") (pintype "passive"))
    )
    (net (code "22") (name "3V3") (class "Default")
      (node (ref "C45") (pin "2") (pinfunction "2_2") (pintype "passive"))
      (node (ref "C48") (pin "2") (pinfunction "2_2") (pintype "passive"))
      (node (ref "C49") (pin "2") (pinfunction "2_2") (pintype "passive"))
      (node (ref "C50") (pin "2") (pinfunction "2_2") (pintype "passive"))
      (node (ref "C51") (pin "2") (pinfunction "2_2") (pintype "passive"))
      (node (ref "C54") (pin "2") (pinfunction "2_2") (pintype "passive"))
      (node (ref "D1") (pin "1") (pinfunction "A_1") (pintype "passive"))
      (node (ref "D2") (pin "1") (pinfunction "A_1") (pintype "passive"))
      (node (ref "D3") (pin "1") (pinfunction "A_1") (pintype "passive"))
      (node (ref "D4") (pin "1") (pinfunction "A_1") (pintype "passive"))
      (node (ref "L3") (pin "1") (pinfunction "1_1") (pintype "passive"))
      (node (ref "R110") (pin "1") (pinfunction "1_1") (pintype "passive"))
      (node (ref "R81") (pin "2") (pinfunction "2_2") (pintype "passive"))
      (node (ref "R87") (pin "2") (pinfunction "2_2") (pintype "passive"))
      (node (ref "R88") (pin "1") (pinfunction "1_1") (pintype "passive"))
      (node (ref "U7") (pin "5") (pinfunction "Vio_5") (pintype "passive"))
      (node (ref "U8") (pin "1") (pinfunction "VBAT_1") (pintype "passive"))
      (node (ref "U8") (pin "24") (pinfunction "VDD_1_24") (pintype "passive"))
      (node (ref "U8") (pin "36") (pinfunction "VDD_2_36") (pintype "passive"))
      (node (ref "U8") (pin "48") (pinfunction "VDD_3_48") (pintype "passive"))
      (node (ref "U9") (pin "2") (pinfunction "VOUT_2") (pintype "passive"))
    )
    (net (code "23") (name "5V") (class "Default")
      (node (ref "C27") (pin "2") (pinfunction "2_2") (pintype "passive"))
      (node (ref "C29") (pin "2") (pinfunction "2_2") (pintype "passive"))
      (node (ref "C30") (pin "2") (pinfunction "2_2") (pintype "passive"))
      (node (ref "C31") (pin "2") (pinfunction "2_2") (pintype "passive"))
      (node (ref "C37") (pin "2") (pinfunction "2_2") (pintype "passive"))
      (node (ref "C46") (pin "2") (pinfunction "2_2") (pintype "passive"))
      (node (ref "L1") (pin "2") (pinfunction "2_2") (pintype "passive"))
      (node (ref "R77") (pin "1") (pinfunction "1_1") (pintype "passive"))
      (node (ref "R85") (pin "2") (pinfunction "2_2") (pintype "passive"))
      (node (ref "R86") (pin "2") (pinfunction "2_2") (pintype "passive"))
      (node (ref "U3") (pin "37") (pinfunction "VREG_37") (pintype "passive"))
      (node (ref "U4") (pin "4") (pinfunction "VCC_4") (pintype "passive"))
      (node (ref "U6") (pin "2") (pinfunction "+Vin_2") (pintype "passive"))
      (node (ref "U7") (pin "3") (pinfunction "Vcc_3") (pintype "passive"))
      (node (ref "U9") (pin "3") (pinfunction "VIN_3") (pintype "passive"))
    )
    (net (code "24") (name "5V_ISOL") (class "Default")
      (node (ref "C36") (pin "2") (pinfunction "2_2") (pintype "passive"))
      (node (ref "U2") (pin "37") (pinfunction "VREG_37") (pintype "passive"))
      (node (ref "U2") (pin "40") (pinfunction "ISOMD_40") (pintype "passive"))
      (node (ref "U6") (pin "4") (pinfunction "+Vo_4") (pintype "passive"))
    )
    (net (code "25") (name "GND") (class "Default")
      (node (ref "C1") (pin "1") (pinfunction "1_1") (pintype "passive"))
      (node (ref "C25") (pin "1") (pinfunction "1_1") (pintype "passive"))
      (node (ref "C29") (pin "1") (pinfunction "1_1") (pintype "passive"))
      (node (ref "C30") (pin "1") (pinfunction "1_1") (pintype "passive"))
      (node (ref "C31") (pin "1") (pinfunction "1_1") (pintype "passive"))
      (node (ref "C33") (pin "1") (pinfunction "1_1") (pintype "passive"))
      (node (ref "C35") (pin "1") (pinfunction "1_1") (pintype "passive"))
      (node (ref "C37") (pin "1") (pinfunction "1_1") (pintype "passive"))
      (node (ref "C39") (pin "1") (pinfunction "1_1") (pintype "passive"))
      (node (ref "C40") (pin "1") (pinfunction "1_1") (pintype "passive"))
      (node (ref "C41") (pin "1") (pinfunction "1_1") (pintype "passive"))
      (node (ref "C42") (pin "1") (pinfunction "1_1") (pintype "passive"))
      (node (ref "C44") (pin "1") (pinfunction "1_1") (pintype "passive"))
      (node (ref "C45") (pin "1") (pinfunction "1_1") (pintype "passive"))
      (node (ref "C46") (pin "1") (pinfunction "1_1") (pintype "passive"))
      (node (ref "C47") (pin "2") (pinfunction "2_2") (pintype "passive"))
      (node (ref "C48") (pin "1") (pinfunction "1_1") (pintype "passive"))
      (node (ref "C49") (pin "1") (pinfunction "1_1") (pintype "passive"))
      (node (ref "C50") (pin "1") (pinfunction "1_1") (pintype "passive"))
      (node (ref "C51") (pin "1") (pinfunction "1_1") (pintype "passive"))
      (node (ref "C52") (pin "1") (pinfunction "1_1") (pintype "passive"))
      (node (ref "C53") (pin "1") (pinfunction "1_1") (pintype "passive"))
      (node (ref "C54") (pin "1") (pinfunction "1_1") (pintype "passive"))
      (node (ref "C55") (pin "1") (pinfunction "1_1") (pintype "passive"))
      (node (ref "C56") (pin "1") (pinfunction "1_1") (pintype "passive"))
      (node (ref "D6") (pin "2") (pinfunction "K_2") (pintype "passive"))
      (node (ref "D7") (pin "1") (pinfunction "A_1") (pintype "passive"))
      (node (ref "D8") (pin "1") (pinfunction "A_1") (pintype "passive"))
      (node (ref "J10") (pin "3") (pinfunction "3_3") (pintype "passive"))
      (node (ref "J6") (pin "2") (pinfunction "2_2") (pintype "passive"))
      (node (ref "Q27") (pin "2") (pinfunction "SOURCE_2") (pintype "passive"))
      (node (ref "R103") (pin "1") (pinfunction "1_1") (pintype "passive"))
      (node (ref "R108") (pin "1") (pinfunction "1_1") (pintype "passive"))
      (node (ref "R109") (pin "1") (pinfunction "1_1") (pintype "passive"))
      (node (ref "R24") (pin "2") (pinfunction "2_2") (pintype "passive"))
      (node (ref "R25") (pin "2") (pinfunction "2_2") (pintype "passive"))
      (node (ref "R75") (pin "1") (pinfunction "1_1") (pintype "passive"))
      (node (ref "R78") (pin "2") (pinfunction "2_2") (pintype "passive"))
      (node (ref "R91") (pin "1") (pinfunction "1_1") (pintype "passive"))
      (node (ref "R99") (pin "1") (pinfunction "1_1") (pintype "passive"))
      (node (ref "U1") (pin "1") (pinfunction "GND_1") (pintype "power_in"))
      (node (ref "U1") (pin "9") (pinfunction "EP_9") (pintype "passive"))
      (node (ref "U11") (pin "1") (pinfunction "VSS_1") (pintype "passive"))
      (node (ref "U3") (pin "30") (pinfunction "V-_30") (pintype "passive"))
      (node (ref "U3") (pin "31") (pinfunction "V-_31") (pintype "passive"))
      (node (ref "U3") (pin "40") (pinfunction "ISOMD_40") (pintype "passive"))
      (node (ref "U4") (pin "2") (pinfunction "GND_2") (pintype "passive"))
      (node (ref "U4") (pin "5") (pinfunction "WP_5") (pintype "passive"))
      (node (ref "U5") (pin "8") (pinfunction "VSS_8") (pintype "passive"))
      (node (ref "U6") (pin "1") (pinfunction "-Vin_1") (pintype "passive"))
      (node (ref "U7") (pin "2") (pinfunction "GND_2") (pintype "passive"))
      (node (ref "U7") (pin "8") (pinfunction "STB_8") (pintype "passive"))
      (node (ref "U7") (pin "9") (pinfunction "EP_9") (pintype "passive"))
      (node (ref "U8") (pin "23") (pinfunction "VSS_1_23") (pintype "passive"))
      (node (ref "U8") (pin "35") (pinfunction "VSS_2_35") (pintype "passive"))
      (node (ref "U8") (pin "44") (pinfunction "BOOT0_44") (pintype "passive"))
      (node (ref "U8") (pin "47") (pinfunction "VSS_3_47") (pintype "passive"))
      (node (ref "U8") (pin "8") (pinfunction "VSS_A_8") (pintype "passive"))
      (node (ref "U9") (pin "1") (pinfunction "VSS_1") (pintype "passive"))
    )
    (net (code "26") (name "MGND") (class "Default")
      (node (ref "C13") (pin "1") (pinfunction "1_1") (pintype "passive"))
      (node (ref "C32") (pin "1") (pinfunction "1_1") (pintype "passive"))
      (node (ref "C34") (pin "1") (pinfunction "1_1") (pintype "passive"))
      (node (ref "C36") (pin "1") (pinfunction "1_1") (pintype "passive"))
      (node (ref "C38") (pin "1") (pinfunction "1_1") (pintype "passive"))
      (node (ref "J5") (pin "2") (pinfunction "2_2") (pintype "passive"))
      (node (ref "Q13") (pin "2") (pinfunction "SOURCE_2") (pintype "passive"))
      (node (ref "R12") (pin "2") (pinfunction "2_2") (pintype "passive"))
      (node (ref "R38") (pin "1") (pinfunction "1_1") (pintype "passive"))
      (node (ref "R62") (pin "1") (pinfunction "1_1") (pintype "passive"))
      (node (ref "R90") (pin "1") (pinfunction "1_1") (pintype "passive"))
      (node (ref "U2") (pin "30") (pinfunction "V-_30") (pintype "passive"))
      (node (ref "U2") (pin "31") (pinfunction "V-_31") (pintype "passive"))
      (node (ref "U3") (pin "1") (pinfunction "V+_1") (pintype "passive"))
      (node (ref "U6") (pin "3") (pinfunction "0V_3") (pintype "passive"))
    )
    (net (code "27") (name "Net-(C27-Pad1)") (class "Default")
      (node (ref "C27") (pin "1") (pinfunction "1_1") (pintype "passive"))
      (node (ref "C28") (pin "2") (pinfunction "2_2") (pintype "passive"))
      (node (ref "R76") (pin "2") (pinfunction "2_2") (pintype "passive"))
    )
    (net (code "28") (name "Net-(D1-K)") (class "Default")
      (node (ref "D1") (pin "2") (pinfunction "K_2") (pintype "passive"))
      (node (ref "R84") (pin "2") (pinfunction "2_2") (pintype "passive"))
    )
    (net (code "29") (name "Net-(D2-K)") (class "Default")
      (node (ref "D2") (pin "2") (pinfunction "K_2") (pintype "passive"))
      (node (ref "R89") (pin "2") (pinfunction "2_2") (pintype "passive"))
    )
    (net (code "30") (name "Net-(D3-K)") (class "Default")
      (node (ref "D3") (pin "2") (pinfunction "K_2") (pintype "passive"))
      (node (ref "R92") (pin "2") (pinfunction "2_2") (pintype "passive"))
    )
    (net (code "31") (name "Net-(D4-K)") (class "Default")
      (node (ref "D4") (pin "2") (pinfunction "K_2") (pintype "passive"))
      (node (ref "R95") (pin "2") (pinfunction "2_2") (pintype "passive"))
    )
    (net (code "32") (name "Net-(D6-A)") (class "Default")
      (node (ref "D6") (pin "1") (pinfunction "A_1") (pintype "passive"))
      (node (ref "R106") (pin "1") (pinfunction "1_1") (pintype "passive"))
    )
    (net (code "33") (name "Net-(Q1-DRAIN)") (class "Default")
      (node (ref "Q1") (pin "3") (pinfunction "DRAIN_3") (pintype "passive"))
      (node (ref "R1") (pin "1") (pinfunction "1_1") (pintype "passive"))
    )
    (net (code "34") (name "Net-(Q1-GATE)") (class "Default")
      (node (ref "Q1") (pin "1") (pinfunction "GATE_1") (pintype "passive"))
      (node (ref "R50") (pin "1") (pinfunction "1_1") (pintype "passive"))
    )
    (net (code "35") (name "Net-(Q2-DRAIN)") (class "Default")
      (node (ref "Q2") (pin "3") (pinfunction "DRAIN_3") (pintype "passive"))
      (node (ref "R2") (pin "1") (pinfunction "1_1") (pintype "passive"))
    )
    (net (code "36") (name "Net-(Q2-GATE)") (class "Default")
      (node (ref "Q2") (pin "1") (pinfunction "GATE_1") (pintype "passive"))
      (node (ref "R51") (pin "1") (pinfunction "1_1") (pintype "passive"))
    )
    (net (code "37") (name "Net-(Q2-SOURCE)") (class "Default")
      (node (ref "Q2") (pin "2") (pinfunction "SOURCE_2") (pintype "passive"))
      (node (ref "R1") (pin "2") (pinfunction "2_2") (pintype "passive"))
      (node (ref "R27") (pin "1") (pinfunction "1_1") (pintype "passive"))
    )
    (net (code "38") (name "Net-(Q3-DRAIN)") (class "Default")
      (node (ref "Q3") (pin "3") (pinfunction "DRAIN_3") (pintype "passive"))
      (node (ref "R3") (pin "1") (pinfunction "1_1") (pintype "passive"))
    )
    (net (code "39") (name "Net-(Q3-GATE)") (class "Default")
      (node (ref "Q3") (pin "1") (pinfunction "GATE_1") (pintype "passive"))
      (node (ref "R52") (pin "1") (pinfunction "1_1") (pintype "passive"))
    )
    (net (code "40") (name "Net-(Q3-SOURCE)") (class "Default")
      (node (ref "Q3") (pin "2") (pinfunction "SOURCE_2") (pintype "passive"))
      (node (ref "R2") (pin "2") (pinfunction "2_2") (pintype "passive"))
      (node (ref "R28") (pin "1") (pinfunction "1_1") (pintype "passive"))
    )
    (net (code "41") (name "Net-(Q4-DRAIN)") (class "Default")
      (node (ref "Q4") (pin "3") (pinfunction "DRAIN_3") (pintype "passive"))
      (node (ref "R4") (pin "1") (pinfunction "1_1") (pintype "passive"))
    )
    (net (code "42") (name "Net-(Q4-GATE)") (class "Default")
      (node (ref "Q4") (pin "1") (pinfunction "GATE_1") (pintype "passive"))
      (node (ref "R53") (pin "1") (pinfunction "1_1") (pintype "passive"))
    )
    (net (code "43") (name "Net-(Q4-SOURCE)") (class "Default")
      (node (ref "Q4") (pin "2") (pinfunction "SOURCE_2") (pintype "passive"))
      (node (ref "R29") (pin "1") (pinfunction "1_1") (pintype "passive"))
      (node (ref "R3") (pin "2") (pinfunction "2_2") (pintype "passive"))
    )
    (net (code "44") (name "Net-(Q5-DRAIN)") (class "Default")
      (node (ref "Q5") (pin "3") (pinfunction "DRAIN_3") (pintype "passive"))
      (node (ref "R5") (pin "1") (pinfunction "1_1") (pintype "passive"))
    )
    (net (code "45") (name "Net-(Q5-GATE)") (class "Default")
      (node (ref "Q5") (pin "1") (pinfunction "GATE_1") (pintype "passive"))
      (node (ref "R54") (pin "1") (pinfunction "1_1") (pintype "passive"))
    )
    (net (code "46") (name "Net-(Q5-SOURCE)") (class "Default")
      (node (ref "Q5") (pin "2") (pinfunction "SOURCE_2") (pintype "passive"))
      (node (ref "R30") (pin "1") (pinfunction "1_1") (pintype "passive"))
      (node (ref "R4") (pin "2") (pinfunction "2_2") (pintype "passive"))
    )
    (net (code "47") (name "Net-(Q6-DRAIN)") (class "Default")
      (node (ref "Q6") (pin "3") (pinfunction "DRAIN_3") (pintype "passive"))
      (node (ref "R6") (pin "1") (pinfunction "1_1") (pintype "passive"))
    )
    (net (code "48") (name "Net-(Q6-GATE)") (class "Default")
      (node (ref "Q6") (pin "1") (pinfunction "GATE_1") (pintype "passive"))
      (node (ref "R55") (pin "1") (pinfunction "1_1") (pintype "passive"))
    )
    (net (code "49") (name "Net-(Q6-SOURCE)") (class "Default")
      (node (ref "Q6") (pin "2") (pinfunction "SOURCE_2") (pintype "passive"))
      (node (ref "R31") (pin "1") (pinfunction "1_1") (pintype "passive"))
      (node (ref "R5") (pin "2") (pinfunction "2_2") (pintype "passive"))
    )
    (net (code "50") (name "Net-(Q7-DRAIN)") (class "Default")
      (node (ref "Q7") (pin "3") (pinfunction "DRAIN_3") (pintype "passive"))
      (node (ref "R7") (pin "1") (pinfunction "1_1") (pintype "passive"))
    )
    (net (code "51") (name "Net-(Q7-GATE)") (class "Default")
      (node (ref "Q7") (pin "1") (pinfunction "GATE_1") (pintype "passive"))
      (node (ref "R56") (pin "1") (pinfunction "1_1") (pintype "passive"))
    )
    (net (code "52") (name "Net-(Q7-SOURCE)") (class "Default")
      (node (ref "Q7") (pin "2") (pinfunction "SOURCE_2") (pintype "passive"))
      (node (ref "R32") (pin "1") (pinfunction "1_1") (pintype "passive"))
      (node (ref "R6") (pin "2") (pinfunction "2_2") (pintype "passive"))
    )
    (net (code "53") (name "Net-(Q8-DRAIN)") (class "Default")
      (node (ref "Q8") (pin "3") (pinfunction "DRAIN_3") (pintype "passive"))
      (node (ref "R8") (pin "1") (pinfunction "1_1") (pintype "passive"))
    )
    (net (code "54") (name "Net-(Q8-GATE)") (class "Default")
      (node (ref "Q8") (pin "1") (pinfunction "GATE_1") (pintype "passive"))
      (node (ref "R57") (pin "1") (pinfunction "1_1") (pintype "passive"))
    )
    (net (code "55") (name "Net-(Q8-SOURCE)") (class "Default")
      (node (ref "Q8") (pin "2") (pinfunction "SOURCE_2") (pintype "passive"))
      (node (ref "R33") (pin "1") (pinfunction "1_1") (pintype "passive"))
      (node (ref "R7") (pin "2") (pinfunction "2_2") (pintype "passive"))
    )
    (net (code "56") (name "Net-(Q9-DRAIN)") (class "Default")
      (node (ref "Q9") (pin "3") (pinfunction "DRAIN_3") (pintype "passive"))
      (node (ref "R9") (pin "1") (pinfunction "1_1") (pintype "passive"))
    )
    (net (code "57") (name "Net-(Q9-GATE)") (class "Default")
      (node (ref "Q9") (pin "1") (pinfunction "GATE_1") (pintype "passive"))
      (node (ref "R58") (pin "1") (pinfunction "1_1") (pintype "passive"))
    )
    (net (code "58") (name "Net-(Q9-SOURCE)") (class "Default")
      (node (ref "Q9") (pin "2") (pinfunction "SOURCE_2") (pintype "passive"))
      (node (ref "R34") (pin "1") (pinfunction "1_1") (pintype "passive"))
      (node (ref "R8") (pin "2") (pinfunction "2_2") (pintype "passive"))
    )
    (net (code "59") (name "Net-(Q10-DRAIN)") (class "Default")
      (node (ref "Q10") (pin "3") (pinfunction "DRAIN_3") (pintype "passive"))
      (node (ref "R10") (pin "1") (pinfunction "1_1") (pintype "passive"))
    )
    (net (code "60") (name "Net-(Q10-GATE)") (class "Default")
      (node (ref "Q10") (pin "1") (pinfunction "GATE_1") (pintype "passive"))
      (node (ref "R59") (pin "1") (pinfunction "1_1") (pintype "passive"))
    )
    (net (code "61") (name "Net-(Q10-SOURCE)") (class "Default")
      (node (ref "Q10") (pin "2") (pinfunction "SOURCE_2") (pintype "passive"))
      (node (ref "R35") (pin "1") (pinfunction "1_1") (pintype "passive"))
      (node (ref "R9") (pin "2") (pinfunction "2_2") (pintype "passive"))
    )
    (net (code "62") (name "Net-(Q11-DRAIN)") (class "Default")
      (node (ref "Q11") (pin "3") (pinfunction "DRAIN_3") (pintype "passive"))
      (node (ref "R11") (pin "1") (pinfunction "1_1") (pintype "passive"))
    )
    (net (code "63") (name "Net-(Q11-GATE)") (class "Default")
      (node (ref "Q11") (pin "1") (pinfunction "GATE_1") (pintype "passive"))
      (node (ref "R60") (pin "1") (pinfunction "1_1") (pintype "passive"))
    )
    (net (code "64") (name "Net-(Q11-SOURCE)") (class "Default")
      (node (ref "Q11") (pin "2") (pinfunction "SOURCE_2") (pintype "passive"))
      (node (ref "R10") (pin "2") (pinfunction "2_2") (pintype "passive"))
      (node (ref "R36") (pin "1") (pinfunction "1_1") (pintype "passive"))
    )
    (net (code "65") (name "Net-(Q12-DRAIN)") (class "Default")
      (node (ref "Q12") (pin "3") (pinfunction "DRAIN_3") (pintype "passive"))
      (node (ref "R12") (pin "1") (pinfunction "1_1") (pintype "passive"))
    )
    (net (code "66") (name "Net-(Q12-GATE)") (class "Default")
      (node (ref "Q12") (pin "1") (pinfunction "GATE_1") (pintype "passive"))
      (node (ref "R61") (pin "1") (pinfunction "1_1") (pintype "passive"))
    )
    (net (code "67") (name "Net-(Q12-SOURCE)") (class "Default")
      (node (ref "Q12") (pin "2") (pinfunction "SOURCE_2") (pintype "passive"))
      (node (ref "R11") (pin "2") (pinfunction "2_2") (pintype "passive"))
      (node (ref "R37") (pin "1") (pinfunction "1_1") (pintype "passive"))
    )
    (net (code "68") (name "Net-(Q13-DRAIN)") (class "Default")
      (node (ref "Q13") (pin "3") (pinfunction "DRAIN_3") (pintype "passive"))
      (node (ref "R13") (pin "1") (pinfunction "1_1") (pintype "passive"))
    )
    (net (code "69") (name "Net-(Q13-GATE)") (class "Default")
      (node (ref "Q13") (pin "1") (pinfunction "GATE_1") (pintype "passive"))
      (node (ref "R63") (pin "1") (pinfunction "1_1") (pintype "passive"))
    )
    (net (code "70") (name "Net-(Q14-DRAIN)") (class "Default")
      (node (ref "Q14") (pin "3") (pinfunction "DRAIN_3") (pintype "passive"))
      (node (ref "R14") (pin "1") (pinfunction "1_1") (pintype "passive"))
    )
    (net (code "71") (name "Net-(Q14-GATE)") (class "Default")
      (node (ref "Q14") (pin "1") (pinfunction "GATE_1") (pintype "passive"))
      (node (ref "R64") (pin "1") (pinfunction "1_1") (pintype "passive"))
    )
    (net (code "72") (name "Net-(Q14-SOURCE)") (class "Default")
      (node (ref "Q14") (pin "2") (pinfunction "SOURCE_2") (pintype "passive"))
      (node (ref "R13") (pin "2") (pinfunction "2_2") (pintype "passive"))
      (node (ref "R39") (pin "1") (pinfunction "1_1") (pintype "passive"))
    )
    (net (code "73") (name "Net-(Q15-DRAIN)") (class "Default")
      (node (ref "Q15") (pin "3") (pinfunction "DRAIN_3") (pintype "passive"))
      (node (ref "R15") (pin "1") (pinfunction "1_1") (pintype "passive"))
    )
    (net (code "74") (name "Net-(Q15-GATE)") (class "Default")
      (node (ref "Q15") (pin "1") (pinfunction "GATE_1") (pintype "passive"))
      (node (ref "R65") (pin "1") (pinfunction "1_1") (pintype "passive"))
    )
    (net (code "75") (name "Net-(Q15-SOURCE)") (class "Default")
      (node (ref "Q15") (pin "2") (pinfunction "SOURCE_2") (pintype "passive"))
      (node (ref "R14") (pin "2") (pinfunction "2_2") (pintype "passive"))
      (node (ref "R40") (pin "1") (pinfunction "1_1") (pintype "passive"))
    )
    (net (code "76") (name "Net-(Q16-DRAIN)") (class "Default")
      (node (ref "Q16") (pin "3") (pinfunction "DRAIN_3") (pintype "passive"))
      (node (ref "R16") (pin "1") (pinfunction "1_1") (pintype "passive"))
    )
    (net (code "77") (name "Net-(Q16-GATE)") (class "Default")
      (node (ref "Q16") (pin "1") (pinfunction "GATE_1") (pintype "passive"))
      (node (ref "R66") (pin "1") (pinfunction "1_1") (pintype "passive"))
    )
    (net (code "78") (name "Net-(Q16-SOURCE)") (class "Default")
      (node (ref "Q16") (pin "2") (pinfunction "SOURCE_2") (pintype "passive"))
      (node (ref "R15") (pin "2") (pinfunction "2_2") (pintype "passive"))
      (node (ref "R41") (pin "1") (pinfunction "1_1") (pintype "passive"))
    )
    (net (code "79") (name "Net-(Q17-DRAIN)") (class "Default")
      (node (ref "Q17") (pin "3") (pinfunction "DRAIN_3") (pintype "passive"))
      (node (ref "R17") (pin "1") (pinfunction "1_1") (pintype "passive"))
    )
    (net (code "80") (name "Net-(Q17-GATE)") (class "Default")
      (node (ref "Q17") (pin "1") (pinfunction "GATE_1") (pintype "passive"))
      (node (ref "R67") (pin "1") (pinfunction "1_1") (pintype "passive"))
    )
    (net (code "81") (name "Net-(Q17-SOURCE)") (class "Default")
      (node (ref "Q17") (pin "2") (pinfunction "SOURCE_2") (pintype "passive"))
      (node (ref "R16") (pin "2") (pinfunction "2_2") (pintype "passive"))
      (node (ref "R42") (pin "1") (pinfunction "1_1") (pintype "passive"))
    )
    (net (code "82") (name "Net-(Q18-DRAIN)") (class "Default")
      (node (ref "Q18") (pin "3") (pinfunction "DRAIN_3") (pintype "passive"))
      (node (ref "R18") (pin "1") (pinfunction "1_1") (pintype "passive"))
    )
    (net (code "83") (name "Net-(Q18-GATE)") (class "Default")
      (node (ref "Q18") (pin "1") (pinfunction "GATE_1") (pintype "passive"))
      (node (ref "R68") (pin "1") (pinfunction "1_1") (pintype "passive"))
    )
    (net (code "84") (name "Net-(Q18-SOURCE)") (class "Default")
      (node (ref "Q18") (pin "2") (pinfunction "SOURCE_2") (pintype "passive"))
      (node (ref "R17") (pin "2") (pinfunction "2_2") (pintype "passive"))
      (node (ref "R43") (pin "1") (pinfunction "1_1") (pintype "passive"))
    )
    (net (code "85") (name "Net-(Q19-DRAIN)") (class "Default")
      (node (ref "Q19") (pin "3") (pinfunction "DRAIN_3") (pintype "passive"))
      (node (ref "R19") (pin "1") (pinfunction "1_1") (pintype "passive"))
    )
    (net (code "86") (name "Net-(Q19-GATE)") (class "Default")
      (node (ref "Q19") (pin "1") (pinfunction "GATE_1") (pintype "passive"))
      (node (ref "R69") (pin "1") (pinfunction "1_1") (pintype "passive"))
    )
    (net (code "87") (name "Net-(Q19-SOURCE)") (class "Default")
      (node (ref "Q19") (pin "2") (pinfunction "SOURCE_2") (pintype "passive"))
      (node (ref "R18") (pin "2") (pinfunction "2_2") (pintype "passive"))
      (node (ref "R44") (pin "1") (pinfunction "1_1") (pintype "passive"))
    )
    (net (code "88") (name "Net-(Q20-DRAIN)") (class "Default")
      (node (ref "Q20") (pin "3") (pinfunction "DRAIN_3") (pintype "passive"))
      (node (ref "R20") (pin "1") (pinfunction "1_1") (pintype "passive"))
    )
    (net (code "89") (name "Net-(Q20-GATE)") (class "Default")
      (node (ref "Q20") (pin "1") (pinfunction "GATE_1") (pintype "passive"))
      (node (ref "R70") (pin "1") (pinfunction "1_1") (pintype "passive"))
    )
    (net (code "90") (name "Net-(Q20-SOURCE)") (class "Default")
      (node (ref "Q20") (pin "2") (pinfunction "SOURCE_2") (pintype "passive"))
      (node (ref "R19") (pin "2") (pinfunction "2_2") (pintype "passive"))
      (node (ref "R45") (pin "1") (pinfunction "1_1") (pintype "passive"))
    )
    (net (code "91") (name "Net-(Q21-DRAIN)") (class "Default")
      (node (ref "Q21") (pin "3") (pinfunction "DRAIN_3") (pintype "passive"))
      (node (ref "R21") (pin "1") (pinfunction "1_1") (pintype "passive"))
    )
    (net (code "92") (name "Net-(Q21-GATE)") (class "Default")
      (node (ref "Q21") (pin "1") (pinfunction "GATE_1") (pintype "passive"))
      (node (ref "R71") (pin "1") (pinfunction "1_1") (pintype "passive"))
    )
    (net (code "93") (name "Net-(Q21-SOURCE)") (class "Default")
      (node (ref "Q21") (pin "2") (pinfunction "SOURCE_2") (pintype "passive"))
      (node (ref "R20") (pin "2") (pinfunction "2_2") (pintype "passive"))
      (node (ref "R46") (pin "1") (pinfunction "1_1") (pintype "passive"))
    )
    (net (code "94") (name "Net-(Q22-DRAIN)") (class "Default")
      (node (ref "Q22") (pin "3") (pinfunction "DRAIN_3") (pintype "passive"))
      (node (ref "R22") (pin "1") (pinfunction "1_1") (pintype "passive"))
    )
    (net (code "95") (name "Net-(Q22-GATE)") (class "Default")
      (node (ref "Q22") (pin "1") (pinfunction "GATE_1") (pintype "passive"))
      (node (ref "R72") (pin "1") (pinfunction "1_1") (pintype "passive"))
    )
    (net (code "96") (name "Net-(Q22-SOURCE)") (class "Default")
      (node (ref "Q22") (pin "2") (pinfunction "SOURCE_2") (pintype "passive"))
      (node (ref "R21") (pin "2") (pinfunction "2_2") (pintype "passive"))
      (node (ref "R47") (pin "1") (pinfunction "1_1") (pintype "passive"))
    )
    (net (code "97") (name "Net-(Q23-DRAIN)") (class "Default")
      (node (ref "Q23") (pin "3") (pinfunction "DRAIN_3") (pintype "passive"))
      (node (ref "R23") (pin "1") (pinfunction "1_1") (pintype "passive"))
    )
    (net (code "98") (name "Net-(Q23-GATE)") (class "Default")
      (node (ref "Q23") (pin "1") (pinfunction "GATE_1") (pintype "passive"))
      (node (ref "R73") (pin "1") (pinfunction "1_1") (pintype "passive"))
    )
    (net (code "99") (name "Net-(Q24-DRAIN)") (class "Default")
      (node (ref "Q24") (pin "3") (pinfunction "DRAIN_3") (pintype "passive"))
      (node (ref "R24") (pin "1") (pinfunction "1_1") (pintype "passive"))
    )
    (net (code "100") (name "Net-(Q24-GATE)") (class "Default")
      (node (ref "Q24") (pin "1") (pinfunction "GATE_1") (pintype "passive"))
      (node (ref "R74") (pin "1") (pinfunction "1_1") (pintype "passive"))
    )
    (net (code "101") (name "Net-(Q24-SOURCE)") (class "Default")
      (node (ref "Q24") (pin "2") (pinfunction "SOURCE_2") (pintype "passive"))
      (node (ref "R23") (pin "2") (pinfunction "2_2") (pintype "passive"))
      (node (ref "R49") (pin "1") (pinfunction "1_1") (pintype "passive"))
    )
    (net (code "102") (name "Net-(Q27-DRAIN)") (class "Default")
      (node (ref "Q27") (pin "3") (pinfunction "DRAIN_3") (pintype "passive"))
      (node (ref "R105") (pin "1") (pinfunction "1_1") (pintype "passive"))
    )
    (net (code "103") (name "Net-(Q27-GATE)") (class "Default")
      (node (ref "Q27") (pin "1") (pinfunction "GATE_1") (pintype "passive"))
      (node (ref "U5") (pin "2") (pinfunction "VEN_2") (pintype "passive"))
    )
    (net (code "104") (name "Net-(Q28-DRAIN)") (class "Default")
      (node (ref "Q28") (pin "3") (pinfunction "DRAIN_3") (pintype "passive"))
      (node (ref "R107") (pin "2") (pinfunction "2_2") (pintype "passive"))
    )
    (net (code "105") (name "Net-(Q28-GATE)") (class "Default")
      (node (ref "Q28") (pin "1") (pinfunction "GATE_1") (pintype "passive"))
      (node (ref "R104") (pin "1") (pinfunction "1_1") (pintype "passive"))
      (node (ref "R105") (pin "2") (pinfunction "2_2") (pintype "passive"))
      (node (ref "U10") (pin "1") (pinfunction "+_1") (pintype "passive"))
    )
    (net (code "106") (name "Net-(R98-Pad2)") (class "Default")
      (node (ref "R98") (pin "2") (pinfunction "2_2") (pintype "passive"))
      (node (ref "SW1") (pin "3") (pinfunction "3_3") (pintype "passive"))
      (node (ref "SW1") (pin "4") (pinfunction "4_4") (pintype "passive"))
    )
    (net (code "107") (name "Net-(R102-Pad1)") (class "Default")
      (node (ref "R102") (pin "1") (pinfunction "1_1") (pintype "passive"))
      (node (ref "R109") (pin "2") (pinfunction "2_2") (pintype "passive"))
    )
    (net (code "108") (name "Net-(U1-BST)") (class "Default")
      (node (ref "C26") (pin "1") (pinfunction "1_1") (pintype "passive"))
      (node (ref "U1") (pin "7") (pinfunction "BST_7") (pintype "passive"))
    )
    (net (code "109") (name "Net-(U1-FB)") (class "Default")
      (node (ref "C28") (pin "1") (pinfunction "1_1") (pintype "passive"))
      (node (ref "R77") (pin "2") (pinfunction "2_2") (pintype "passive"))
      (node (ref "R78") (pin "1") (pinfunction "1_1") (pintype "passive"))
      (node (ref "U1") (pin "5") (pinfunction "FB_5") (pintype "power_in"))
    )
    (net (code "110") (name "Net-(U1-RON)") (class "Default")
      (node (ref "R25") (pin "1") (pinfunction "1_1") (pintype "passive"))
      (node (ref "U1") (pin "4") (pinfunction "RON_4") (pintype "power_in"))
    )
    (net (code "111") (name "Net-(U1-SW)") (class "Default")
      (node (ref "C26") (pin "2") (pinfunction "2_2") (pintype "passive"))
      (node (ref "L1") (pin "1") (pinfunction "1_1") (pintype "passive"))
      (node (ref "R76") (pin "1") (pinfunction "1_1") (pintype "passive"))
      (node (ref "U1") (pin "8") (pinfunction "SW_8") (pintype "power_in"))
    )
    (net (code "112") (name "Net-(U2-C0)") (class "Default")
      (node (ref "R62") (pin "2") (pinfunction "2_2") (pintype "passive"))
      (node (ref "U2") (pin "26") (pinfunction "C0_26") (pintype "passive"))
    )
    (net (code "113") (name "Net-(U2-C1)") (class "Default")
      (node (ref "C12") (pin "1") (pinfunction "1_1") (pintype "passive"))
      (node (ref "C13") (pin "2") (pinfunction "2_2") (pintype "passive"))
      (node (ref "R37") (pin "2") (pinfunction "2_2") (pintype "passive"))
      (node (ref "U2") (pin "24") (pinfunction "C1_24") (pintype "passive"))
    )
    (net (code "114") (name "Net-(U2-C2)") (class "Default")
      (node (ref "C11") (pin "1") (pinfunction "1_1") (pintype "passive"))
      (node (ref "C12") (pin "2") (pinfunction "2_2") (pintype "passive"))
      (node (ref "R36") (pin "2") (pinfunction "2_2") (pintype "passive"))
      (node (ref "U2") (pin "22") (pinfunction "C2_22") (pintype "passive"))
    )
    (net (code "115") (name "Net-(U2-C3)") (class "Default")
      (node (ref "C10") (pin "1") (pinfunction "1_1") (pintype "passive"))
      (node (ref "C11") (pin "2") (pinfunction "2_2") (pintype "passive"))
      (node (ref "R35") (pin "2") (pinfunction "2_2") (pintype "passive"))
      (node (ref "U2") (pin "20") (pinfunction "C3_20") (pintype "passive"))
    )
    (net (code "116") (name "Net-(U2-C4)") (class "Default")
      (node (ref "C10") (pin "2") (pinfunction "2_2") (pintype "passive"))
      (node (ref "C9") (pin "1") (pinfunction "1_1") (pintype "passive"))
      (node (ref "R34") (pin "2") (pinfunction "2_2") (pintype "passive"))
      (node (ref "U2") (pin "18") (pinfunction "C4_18") (pintype "passive"))
    )
    (net (code "117") (name "Net-(U2-C5)") (class "Default")
      (node (ref "C8") (pin "1") (pinfunction "1_1") (pintype "passive"))
      (node (ref "C9") (pin "2") (pinfunction "2_2") (pintype "passive"))
      (node (ref "R33") (pin "2") (pinfunction "2_2") (pintype "passive"))
      (node (ref "U2") (pin "16") (pinfunction "C5_16") (pintype "passive"))
    )
    (net (code "118") (name "Net-(U2-C6)") (class "Default")
      (node (ref "C7") (pin "1") (pinfunction "1_1") (pintype "passive"))
      (node (ref "C8") (pin "2") (pinfunction "2_2") (pintype "passive"))
      (node (ref "R32") (pin "2") (pinfunction "2_2") (pintype "passive"))
      (node (ref "U2") (pin "14") (pinfunction "C6_14") (pintype "passive"))
    )
    (net (code "119") (name "Net-(U2-C7)") (class "Default")
      (node (ref "C6") (pin "1") (pinfunction "1_1") (pintype "passive"))
      (node (ref "C7") (pin "2") (pinfunction "2_2") (pintype "passive"))
      (node (ref "R31") (pin "2") (pinfunction "2_2") (pintype "passive"))
      (node (ref "U2") (pin "12") (pinfunction "C7_12") (pintype "passive"))
    )
    (net (code "120") (name "Net-(U2-C8)") (class "Default")
      (node (ref "C5") (pin "1") (pinfunction "1_1") (pintype "passive"))
      (node (ref "C6") (pin "2") (pinfunction "2_2") (pintype "passive"))
      (node (ref "R30") (pin "2") (pinfunction "2_2") (pintype "passive"))
      (node (ref "U2") (pin "10") (pinfunction "C8_10") (pintype "passive"))
    )
    (net (code "121") (name "Net-(U2-C9)") (class "Default")
      (node (ref "C4") (pin "1") (pinfunction "1_1") (pintype "passive"))
      (node (ref "C5") (pin "2") (pinfunction "2_2") (pintype "passive"))
      (node (ref "R29") (pin "2") (pinfunction "2_2") (pintype "passive"))
      (node (ref "U2") (pin "8") (pinfunction "C9_8") (pintype "passive"))
    )
    (net (code "122") (name "Net-(U2-C10)") (class "Default")
      (node (ref "C3") (pin "1") (pinfunction "1_1") (pintype "passive"))
      (node (ref "C4") (pin "2") (pinfunction "2_2") (pintype "passive"))
      (node (ref "R28") (pin "2") (pinfunction "2_2") (pintype "passive"))
      (node (ref "U2") (pin "6") (pinfunction "C10_6") (pintype "passive"))
    )
    (net (code "123") (name "Net-(U2-C11)") (class "Default")
      (node (ref "C2") (pin "1") (pinfunction "1_1") (pintype "passive"))
      (node (ref "C3") (pin "2") (pinfunction "2_2") (pintype "passive"))
      (node (ref "R27") (pin "2") (pinfunction "2_2") (pintype "passive"))
      (node (ref "U2") (pin "4") (pinfunction "C11_4") (pintype "passive"))
    )
    (net (code "124") (name "Net-(U2-C12)") (class "Default")
      (node (ref "C2") (pin "2") (pinfunction "2_2") (pintype "passive"))
      (node (ref "R26") (pin "2") (pinfunction "2_2") (pintype "passive"))
      (node (ref "U2") (pin "2") (pinfunction "C12_2") (pintype "passive"))
    )
    (net (code "125") (name "Net-(U2-DTEN)") (class "Default")
      (node (ref "J2") (pin "1") (pinfunction "1_1") (pintype "passive"))
      (node (ref "U2") (pin "36") (pinfunction "DTEN_36") (pintype "passive"))
    )
    (net (code "126") (name "Net-(U2-GPI03)") (class "Default")
      (node (ref "C38") (pin "2") (pinfunction "2_2") (pintype "passive"))
      (node (ref "J5") (pin "1") (pinfunction "1_1") (pintype "passive"))
      (node (ref "R93") (pin "2") (pinfunction "2_2") (pintype "passive"))
      (node (ref "U2") (pin "29") (pinfunction "GPI03_29") (pintype "passive"))
    )
    (net (code "127") (name "Net-(U2-IBIAS)") (class "Default")
      (node (ref "R82") (pin "2") (pinfunction "2_2") (pintype "passive"))
      (node (ref "U2") (pin "45") (pinfunction "IBIAS_45") (pintype "passive"))
    )
    (net (code "128") (name "Net-(U2-ICMP)") (class "Default")
      (node (ref "R82") (pin "1") (pinfunction "1_1") (pintype "passive"))
      (node (ref "R90") (pin "2") (pinfunction "2_2") (pintype "passive"))
      (node (ref "U2") (pin "46") (pinfunction "ICMP_46") (pintype "passive"))
    )
    (net (code "129") (name "Net-(U2-IMB)") (class "Default")
      (node (ref "L2") (pin "3") (pinfunction "3_3") (pintype "passive"))
      (node (ref "R96") (pin "2") (pinfunction "2_2") (pintype "passive"))
      (node (ref "U2") (pin "47") (pinfunction "IMB_47") (pintype "passive"))
    )
    (net (code "130") (name "Net-(U2-IPB)") (class "Default")
      (node (ref "L2") (pin "4") (pinfunction "4_4") (pintype "passive"))
      (node (ref "R96") (pin "1") (pinfunction "1_1") (pintype "passive"))
      (node (ref "U2") (pin "48") (pinfunction "IPB_48") (pintype "passive"))
    )
    (net (code "131") (name "Net-(U2-S1)") (class "Default")
      (node (ref "R61") (pin "2") (pinfunction "2_2") (pintype "passive"))
      (node (ref "U2") (pin "25") (pinfunction "S1_25") (pintype "passive"))
    )
    (net (code "132") (name "Net-(U2-S2)") (class "Default")
      (node (ref "R60") (pin "2") (pinfunction "2_2") (pintype "passive"))
      (node (ref "U2") (pin "23") (pinfunction "S2_23") (pintype "passive"))
    )
    (net (code "133") (name "Net-(U2-S3)") (class "Default")
      (node (ref "R59") (pin "2") (pinfunction "2_2") (pintype "passive"))
      (node (ref "U2") (pin "21") (pinfunction "S3_21") (pintype "passive"))
    )
    (net (code "134") (name "Net-(U2-S4)") (class "Default")
      (node (ref "R58") (pin "2") (pinfunction "2_2") (pintype "passive"))
      (node (ref "U2") (pin "19") (pinfunction "S4_19") (pintype "passive"))
    )
    (net (code "135") (name "Net-(U2-S5)") (class "Default")
      (node (ref "R57") (pin "2") (pinfunction "2_2") (pintype "passive"))
      (node (ref "U2") (pin "17") (pinfunction "S5_17") (pintype "passive"))
    )
    (net (code "136") (name "Net-(U2-S6)") (class "Default")
      (node (ref "R56") (pin "2") (pinfunction "2_2") (pintype "passive"))
      (node (ref "U2") (pin "15") (pinfunction "S6_15") (pintype "passive"))
    )
    (net (code "137") (name "Net-(U2-S7)") (class "Default")
      (node (ref "R55") (pin "2") (pinfunction "2_2") (pintype "passive"))
      (node (ref "U2") (pin "13") (pinfunction "S7_13") (pintype "passive"))
    )
    (net (code "138") (name "Net-(U2-S8)") (class "Default")
      (node (ref "R54") (pin "2") (pinfunction "2_2") (pintype "passive"))
      (node (ref "U2") (pin "11") (pinfunction "S8_11") (pintype "passive"))
    )
    (net (code "139") (name "Net-(U2-S9)") (class "Default")
      (node (ref "R53") (pin "2") (pinfunction "2_2") (pintype "passive"))
      (node (ref "U2") (pin "9") (pinfunction "S9_9") (pintype "passive"))
    )
    (net (code "140") (name "Net-(U2-S10)") (class "Default")
      (node (ref "R52") (pin "2") (pinfunction "2_2") (pintype "passive"))
      (node (ref "U2") (pin "7") (pinfunction "S10_7") (pintype "passive"))
    )
    (net (code "141") (name "Net-(U2-S11)") (class "Default")
      (node (ref "R51") (pin "2") (pinfunction "2_2") (pintype "passive"))
      (node (ref "U2") (pin "5") (pinfunction "S11_5") (pintype "passive"))
    )
    (net (code "142") (name "Net-(U2-S12)") (class "Default")
      (node (ref "R50") (pin "2") (pinfunction "2_2") (pintype "passive"))
      (node (ref "U2") (pin "3") (pinfunction "S12_3") (pintype "passive"))
    )
    (net (code "143") (name "Net-(U2-VREF1)") (class "Default")
      (node (ref "C34") (pin "2") (pinfunction "2_2") (pintype "passive"))
      (node (ref "U2") (pin "35") (pinfunction "VREF1_35") (pintype "passive"))
    )
    (net (code "144") (name "Net-(U2-VREF2)") (class "Default")
      (node (ref "C32") (pin "2") (pinfunction "2_2") (pintype "passive"))
      (node (ref "R93") (pin "1") (pinfunction "1_1") (pintype "passive"))
      (node (ref "U2") (pin "34") (pinfunction "VREF2_34") (pintype "passive"))
    )
    (net (code "145") (name "Net-(U2-WDT)") (class "Default")
      (node (ref "J1") (pin "1") (pinfunction "1_1") (pintype "passive"))
      (node (ref "U2") (pin "39") (pinfunction "WDT_39") (pintype "passive"))
    )
    (net (code "146") (name "Net-(U3-C0)") (class "Default")
      (node (ref "R75") (pin "2") (pinfunction "2_2") (pintype "passive"))
      (node (ref "U3") (pin "26") (pinfunction "C0_26") (pintype "passive"))
    )
    (net (code "147") (name "Net-(U3-C1)") (class "Default")
      (node (ref "C24") (pin "1") (pinfunction "1_1") (pintype "passive"))
      (node (ref "C25") (pin "2") (pinfunction "2_2") (pintype "passive"))
      (node (ref "R49") (pin "2") (pinfunction "2_2") (pintype "passive"))
      (node (ref "U3") (pin "24") (pinfunction "C1_24") (pintype "passive"))
    )
    (net (code "148") (name "Net-(U3-C2)") (class "Default")
      (node (ref "C23") (pin "1") (pinfunction "1_1") (pintype "passive"))
      (node (ref "C24") (pin "2") (pinfunction "2_2") (pintype "passive"))
      (node (ref "R48") (pin "2") (pinfunction "2_2") (pintype "passive"))
      (node (ref "U3") (pin "22") (pinfunction "C2_22") (pintype "passive"))
    )
    (net (code "149") (name "Net-(U3-C3)") (class "Default")
      (node (ref "C22") (pin "1") (pinfunction "1_1") (pintype "passive"))
      (node (ref "C23") (pin "2") (pinfunction "2_2") (pintype "passive"))
      (node (ref "R47") (pin "2") (pinfunction "2_2") (pintype "passive"))
      (node (ref "U3") (pin "20") (pinfunction "C3_20") (pintype "passive"))
    )
    (net (code "150") (name "Net-(U3-C4)") (class "Default")
      (node (ref "C21") (pin "1") (pinfunction "1_1") (pintype "passive"))
      (node (ref "C22") (pin "2") (pinfunction "2_2") (pintype "passive"))
      (node (ref "R46") (pin "2") (pinfunction "2_2") (pintype "passive"))
      (node (ref "U3") (pin "18") (pinfunction "C4_18") (pintype "passive"))
    )
    (net (code "151") (name "Net-(U3-C5)") (class "Default")
      (node (ref "C20") (pin "1") (pinfunction "1_1") (pintype "passive"))
      (node (ref "C21") (pin "2") (pinfunction "2_2") (pintype "passive"))
      (node (ref "R45") (pin "2") (pinfunction "2_2") (pintype "passive"))
      (node (ref "U3") (pin "16") (pinfunction "C5_16") (pintype "passive"))
    )
    (net (code "152") (name "Net-(U3-C6)") (class "Default")
      (node (ref "C19") (pin "1") (pinfunction "1_1") (pintype "passive"))
      (node (ref "C20") (pin "2") (pinfunction "2_2") (pintype "passive"))
      (node (ref "R44") (pin "2") (pinfunction "2_2") (pintype "passive"))
      (node (ref "U3") (pin "14") (pinfunction "C6_14") (pintype "passive"))
    )
    (net (code "153") (name "Net-(U3-C7)") (class "Default")
      (node (ref "C18") (pin "1") (pinfunction "1_1") (pintype "passive"))
      (node (ref "C19") (pin "2") (pinfunction "2_2") (pintype "passive"))
      (node (ref "R43") (pin "2") (pinfunction "2_2") (pintype "passive"))
      (node (ref "U3") (pin "12") (pinfunction "C7_12") (pintype "passive"))
    )
    (net (code "154") (name "Net-(U3-C8)") (class "Default")
      (node (ref "C17") (pin "1") (pinfunction "1_1") (pintype "passive"))
      (node (ref "C18") (pin "2") (pinfunction "2_2") (pintype "passive"))
      (node (ref "R42") (pin "2") (pinfunction "2_2") (pintype "passive"))
      (node (ref "U3") (pin "10") (pinfunction "C8_10") (pintype "passive"))
    )
    (net (code "155") (name "Net-(U3-C9)") (class "Default")
      (node (ref "C16") (pin "1") (pinfunction "1_1") (pintype "passive"))
      (node (ref "C17") (pin "2") (pinfunction "2_2") (pintype "passive"))
      (node (ref "R41") (pin "2") (pinfunction "2_2") (pintype "passive"))
      (node (ref "U3") (pin "8") (pinfunction "C9_8") (pintype "passive"))
    )
    (net (code "156") (name "Net-(U3-C10)") (class "Default")
      (node (ref "C15") (pin "1") (pinfunction "1_1") (pintype "passive"))
      (node (ref "C16") (pin "2") (pinfunction "2_2") (pintype "passive"))
      (node (ref "R40") (pin "2") (pinfunction "2_2") (pintype "passive"))
      (node (ref "U3") (pin "6") (pinfunction "C10_6") (pintype "passive"))
    )
    (net (code "157") (name "Net-(U3-C11)") (class "Default")
      (node (ref "C14") (pin "1") (pinfunction "1_1") (pintype "passive"))
      (node (ref "C15") (pin "2") (pinfunction "2_2") (pintype "passive"))
      (node (ref "R39") (pin "2") (pinfunction "2_2") (pintype "passive"))
      (node (ref "U3") (pin "4") (pinfunction "C11_4") (pintype "passive"))
    )
    (net (code "158") (name "Net-(U3-C12)") (class "Default")
      (node (ref "C14") (pin "2") (pinfunction "2_2") (pintype "passive"))
      (node (ref "R38") (pin "2") (pinfunction "2_2") (pintype "passive"))
      (node (ref "U3") (pin "2") (pinfunction "C12_2") (pintype "passive"))
    )
    (net (code "159") (name "Net-(U3-DTEN)") (class "Default")
      (node (ref "J4") (pin "1") (pinfunction "1_1") (pintype "passive"))
      (node (ref "U3") (pin "36") (pinfunction "DTEN_36") (pintype "passive"))
    )
    (net (code "160") (name "Net-(U3-GPI03)") (class "Default")
      (node (ref "C39") (pin "2") (pinfunction "2_2") (pintype "passive"))
      (node (ref "J6") (pin "1") (pinfunction "1_1") (pintype "passive"))
      (node (ref "R94") (pin "2") (pinfunction "2_2") (pintype "passive"))
      (node (ref "U3") (pin "29") (pinfunction "GPI03_29") (pintype "passive"))
    )
    (net (code "161") (name "Net-(U3-IBIAS)") (class "Default")
      (node (ref "R83") (pin "2") (pinfunction "2_2") (pintype "passive"))
      (node (ref "U3") (pin "45") (pinfunction "IBIAS_45") (pintype "passive"))
    )
    (net (code "162") (name "Net-(U3-ICMP)") (class "Default")
      (node (ref "R83") (pin "1") (pinfunction "1_1") (pintype "passive"))
      (node (ref "R91") (pin "2") (pinfunction "2_2") (pintype "passive"))
      (node (ref "U3") (pin "46") (pinfunction "ICMP_46") (pintype "passive"))
    )
    (net (code "163") (name "Net-(U3-IMB)") (class "Default")
      (node (ref "L2") (pin "2") (pinfunction "2_2") (pintype "passive"))
      (node (ref "R97") (pin "2") (pinfunction "2_2") (pintype "passive"))
      (node (ref "U3") (pin "47") (pinfunction "IMB_47") (pintype "passive"))
    )
    (net (code "164") (name "Net-(U3-IPB)") (class "Default")
      (node (ref "L2") (pin "1") (pinfunction "1_1") (pintype "passive"))
      (node (ref "R97") (pin "1") (pinfunction "1_1") (pintype "passive"))
      (node (ref "U3") (pin "48") (pinfunction "IPB_48") (pintype "passive"))
    )
    (net (code "165") (name "Net-(U3-S1)") (class "Default")
      (node (ref "R74") (pin "2") (pinfunction "2_2") (pintype "passive"))
      (node (ref "U3") (pin "25") (pinfunction "S1_25") (pintype "passive"))
    )
    (net (code "166") (name "Net-(U3-S2)") (class "Default")
      (node (ref "R73") (pin "2") (pinfunction "2_2") (pintype "passive"))
      (node (ref "U3") (pin "23") (pinfunction "S2_23") (pintype "passive"))
    )
    (net (code "167") (name "Net-(U3-S3)") (class "Default")
      (node (ref "R72") (pin "2") (pinfunction "2_2") (pintype "passive"))
      (node (ref "U3") (pin "21") (pinfunction "S3_21") (pintype "passive"))
    )
    (net (code "168") (name "Net-(U3-S4)") (class "Default")
      (node (ref "R71") (pin "2") (pinfunction "2_2") (pintype "passive"))
      (node (ref "U3") (pin "19") (pinfunction "S4_19") (pintype "passive"))
    )
    (net (code "169") (name "Net-(U3-S5)") (class "Default")
      (node (ref "R70") (pin "2") (pinfunction "2_2") (pintype "passive"))
      (node (ref "U3") (pin "17") (pinfunction "S5_17") (pintype "passive"))
    )
    (net (code "170") (name "Net-(U3-S6)") (class "Default")
      (node (ref "R69") (pin "2") (pinfunction "2_2") (pintype "passive"))
      (node (ref "U3") (pin "15") (pinfunction "S6_15") (pintype "passive"))
    )
    (net (code "171") (name "Net-(U3-S7)") (class "Default")
      (node (ref "R68") (pin "2") (pinfunction "2_2") (pintype "passive"))
      (node (ref "U3") (pin "13") (pinfunction "S7_13") (pintype "passive"))
    )
    (net (code "172") (name "Net-(U3-S8)") (class "Default")
      (node (ref "R67") (pin "2") (pinfunction "2_2") (pintype "passive"))
      (node (ref "U3") (pin "11") (pinfunction "S8_11") (pintype "passive"))
    )
    (net (code "173") (name "Net-(U3-S9)") (class "Default")
      (node (ref "R66") (pin "2") (pinfunction "2_2") (pintype "passive"))
      (node (ref "U3") (pin "9") (pinfunction "S9_9") (pintype "passive"))
    )
    (net (code "174") (name "Net-(U3-S10)") (class "Default")
      (node (ref "R65") (pin "2") (pinfunction "2_2") (pintype "passive"))
      (node (ref "U3") (pin "7") (pinfunction "S10_7") (pintype "passive"))
    )
    (net (code "175") (name "Net-(U3-S11)") (class "Default")
      (node (ref "R64") (pin "2") (pinfunction "2_2") (pintype "passive"))
      (node (ref "U3") (pin "5") (pinfunction "S11_5") (pintype "passive"))
    )
    (net (code "176") (name "Net-(U3-S12)") (class "Default")
      (node (ref "R63") (pin "2") (pinfunction "2_2") (pintype "passive"))
      (node (ref "U3") (pin "3") (pinfunction "S12_3") (pintype "passive"))
    )
    (net (code "177") (name "Net-(U3-VREF1)") (class "Default")
      (node (ref "C35") (pin "2") (pinfunction "2_2") (pintype "passive"))
      (node (ref "U3") (pin "35") (pinfunction "VREF1_35") (pintype "passive"))
    )
    (net (code "178") (name "Net-(U3-VREF2)") (class "Default")
      (node (ref "C33") (pin "2") (pinfunction "2_2") (pintype "passive"))
      (node (ref "R94") (pin "1") (pinfunction "1_1") (pintype "passive"))
      (node (ref "U3") (pin "34") (pinfunction "VREF2_34") (pintype "passive"))
    )
    (net (code "179") (name "Net-(U3-WDT)") (class "Default")
      (node (ref "J3") (pin "1") (pinfunction "1_1") (pintype "passive"))
      (node (ref "U3") (pin "39") (pinfunction "WDT_39") (pintype "passive"))
    )
    (net (code "180") (name "Net-(U5-BAT)") (class "Default")
      (node (ref "C47") (pin "1") (pinfunction "1_1") (pintype "passive"))
      (node (ref "R107") (pin "1") (pinfunction "1_1") (pintype "passive"))
      (node (ref "R108") (pin "2") (pinfunction "2_2") (pintype "passive"))
      (node (ref "U5") (pin "4") (pinfunction "BAT_4") (pintype "passive"))
    )
    (net (code "181") (name "Net-(U5-CE)") (class "Default")
      (node (ref "C40") (pin "2") (pinfunction "2_2") (pintype "passive"))
      (node (ref "F2") (pin "1") (pinfunction "1_1") (pintype "passive"))
      (node (ref "U5") (pin "5") (pinfunction "CE_5") (pintype "passive"))
      (node (ref "U5") (pin "6") (pinfunction "REGIN_6") (pintype "passive"))
    )
    (net (code "182") (name "Net-(U5-P3{slash}SDA)") (class "Default")
      (node (ref "R79") (pin "1") (pinfunction "1_1") (pintype "passive"))
      (node (ref "R87") (pin "1") (pinfunction "1_1") (pintype "passive"))
      (node (ref "U5") (pin "14") (pinfunction "P3/SDA_14") (pintype "passive"))
    )
    (net (code "183") (name "Net-(U5-P4{slash}SCL)") (class "Default")
      (node (ref "R80") (pin "1") (pinfunction "1_1") (pintype "passive"))
      (node (ref "R81") (pin "1") (pinfunction "1_1") (pintype "passive"))
      (node (ref "U5") (pin "13") (pinfunction "P4/SCL_13") (pintype "passive"))
    )
    (net (code "184") (name "Net-(U5-P5{slash}HDQ)") (class "Default")
      (node (ref "J7") (pin "1") (pinfunction "1_1") (pintype "passive"))
      (node (ref "U5") (pin "12") (pinfunction "P5/HDQ_12") (pintype "passive"))
    )
    (net (code "185") (name "Net-(U5-P6{slash}TS)") (class "Default")
      (node (ref "J8") (pin "2") (pinfunction "2_2") (pintype "passive"))
      (node (ref "U5") (pin "11") (pinfunction "P6/TS_11") (pintype "passive"))
    )
    (net (code "186") (name "Net-(U5-SRN)") (class "Default")
      (node (ref "C42") (pin "2") (pinfunction "2_2") (pintype "passive"))
      (node (ref "C43") (pin "2") (pinfunction "2_2") (pintype "passive"))
      (node (ref "R102") (pin "2") (pinfunction "2_2") (pintype "passive"))
      (node (ref "U5") (pin "10") (pinfunction "SRN_10") (pintype "passive"))
    )
    (net (code "187") (name "Net-(U5-SRP)") (class "Default")
      (node (ref "C43") (pin "1") (pinfunction "1_1") (pintype "passive"))
      (node (ref "C44") (pin "2") (pinfunction "2_2") (pintype "passive"))
      (node (ref "R103") (pin "2") (pinfunction "2_2") (pintype "passive"))
      (node (ref "U5") (pin "9") (pinfunction "SRP_9") (pintype "passive"))
    )
    (net (code "188") (name "Net-(U8-NRST)") (class "Default")
      (node (ref "C52") (pin "2") (pinfunction "2_2") (pintype "passive"))
      (node (ref "R110") (pin "2") (pinfunction "2_2") (pintype "passive"))
      (node (ref "U8") (pin "7") (pinfunction "NRST_7") (pintype "passive"))
    )
    (net (code "189") (name "Net-(U8-PA3)") (class "Default")
      (node (ref "R106") (pin "2") (pinfunction "2_2") (pintype "passive"))
      (node (ref "U8") (pin "13") (pinfunction "PA3_13") (pintype "passive"))
    )
    (net (code "190") (name "Net-(U8-VDD_A)") (class "Default")
      (node (ref "C53") (pin "2") (pinfunction "2_2") (pintype "passive"))
      (node (ref "L3") (pin "2") (pinfunction "2_2") (pintype "passive"))
      (node (ref "U8") (pin "9") (pinfunction "VDD_A_9") (pintype "passive"))
    )
    (net (code "191") (name "Net-(U11-VOUT)") (class "Default")
      (node (ref "C56") (pin "2") (pinfunction "2_2") (pintype "passive"))
      (node (ref "F2") (pin "2") (pinfunction "2_2") (pintype "passive"))
      (node (ref "U11") (pin "2") (pinfunction "VOUT_2") (pintype "passive"))
    )
    (net (code "192") (name "Vb+") (class "Default")
      (node (ref "F1") (pin "2") (pinfunction "2_2") (pintype "passive"))
      (node (ref "Q1") (pin "2") (pinfunction "SOURCE_2") (pintype "passive"))
      (node (ref "Q28") (pin "2") (pinfunction "SOURCE_2") (pintype "passive"))
      (node (ref "R104") (pin "2") (pinfunction "2_2") (pintype "passive"))
      (node (ref "R26") (pin "1") (pinfunction "1_1") (pintype "passive"))
      (node (ref "U10") (pin "2") (pinfunction "-_2") (pintype "passive"))
      (node (ref "U2") (pin "1") (pinfunction "V+_1") (pintype "passive"))
    )
    (net (code "193") (name "Vbf") (class "Default")
      (node (ref "C1") (pin "2") (pinfunction "2_2") (pintype "passive"))
      (node (ref "F1") (pin "1") (pinfunction "1_1") (pintype "passive"))
      (node (ref "R98") (pin "1") (pinfunction "1_1") (pintype "passive"))
      (node (ref "U1") (pin "2") (pinfunction "VIN_2") (pintype "power_in"))
    )
    (net (code "194") (name "Vreg") (class "Default")
      (node (ref "C41") (pin "2") (pinfunction "2_2") (pintype "passive"))
      (node (ref "J8") (pin "1") (pinfunction "1_1") (pintype "passive"))
      (node (ref "U5") (pin "7") (pinfunction "REG25_7") (pintype "passive"))
    )
    (net (code "195") (name "unconnected-(U1-PG-Pad6)") (class "Default")
      (node (ref "U1") (pin "6") (pinfunction "PG_6") (pintype "open_collector"))
    )
    (net (code "196") (name "unconnected-(U2-CSB(IMA)-Pad41)") (class "Default")
      (node (ref "U2") (pin "41") (pinfunction "CSB(IMA)_41") (pintype "passive"))
    )
    (net (code "197") (name "unconnected-(U2-DRIVE-Pad38)") (class "Default")
      (node (ref "U2") (pin "38") (pinfunction "DRIVE_38") (pintype "passive"))
    )
    (net (code "198") (name "unconnected-(U2-GPI01-Pad27)") (class "Default")
      (node (ref "U2") (pin "27") (pinfunction "GPI01_27") (pintype "passive"))
    )
    (net (code "199") (name "unconnected-(U2-GPI02-Pad28)") (class "Default")
      (node (ref "U2") (pin "28") (pinfunction "GPI02_28") (pintype "passive"))
    )
    (net (code "200") (name "unconnected-(U2-GPI04-Pad32)") (class "Default")
      (node (ref "U2") (pin "32") (pinfunction "GPI04_32") (pintype "passive"))
    )
    (net (code "201") (name "unconnected-(U2-GPI05-Pad33)") (class "Default")
      (node (ref "U2") (pin "33") (pinfunction "GPI05_33") (pintype "passive"))
    )
    (net (code "202") (name "unconnected-(U2-SCK(IPA)-Pad42)") (class "Default")
      (node (ref "U2") (pin "42") (pinfunction "SCK(IPA)_42") (pintype "passive"))
    )
    (net (code "203") (name "unconnected-(U2-SDI(NC)-Pad43)") (class "Default")
      (node (ref "U2") (pin "43") (pinfunction "SDI(NC)_43") (pintype "passive"))
    )
    (net (code "204") (name "unconnected-(U2-SDO(NC)-Pad44)") (class "Default")
      (node (ref "U2") (pin "44") (pinfunction "SDO(NC)_44") (pintype "passive"))
    )
    (net (code "205") (name "unconnected-(U3-DRIVE-Pad38)") (class "Default")
      (node (ref "U3") (pin "38") (pinfunction "DRIVE_38") (pintype "passive"))
    )
    (net (code "206") (name "unconnected-(U3-GPI01-Pad27)") (class "Default")
      (node (ref "U3") (pin "27") (pinfunction "GPI01_27") (pintype "passive"))
    )
    (net (code "207") (name "unconnected-(U3-GPI02-Pad28)") (class "Default")
      (node (ref "U3") (pin "28") (pinfunction "GPI02_28") (pintype "passive"))
    )
    (net (code "208") (name "unconnected-(U5-P1-Pad3)") (class "Default")
      (node (ref "U5") (pin "3") (pinfunction "P1_3") (pintype "passive"))
    )
    (net (code "209") (name "unconnected-(U5-P2-Pad1)") (class "Default")
      (node (ref "U5") (pin "1") (pinfunction "P2_1") (pintype "passive"))
    )
    (net (code "210") (name "unconnected-(U8-PA0-Pad10)") (class "Default")
      (node (ref "U8") (pin "10") (pinfunction "PA0_10") (pintype "passive"))
    )
    (net (code "211") (name "unconnected-(U8-PA1-Pad11)") (class "Default")
      (node (ref "U8") (pin "11") (pinfunction "PA1_11") (pintype "passive"))
    )
    (net (code "212") (name "unconnected-(U8-PA2-Pad12)") (class "Default")
      (node (ref "U8") (pin "12") (pinfunction "PA2_12") (pintype "passive"))
    )
    (net (code "213") (name "unconnected-(U8-PA8-Pad29)") (class "Default")
      (node (ref "U8") (pin "29") (pinfunction "PA8_29") (pintype "passive"))
    )
    (net (code "214") (name "unconnected-(U8-PA9-Pad30)") (class "Default")
      (node (ref "U8") (pin "30") (pinfunction "PA9_30") (pintype "passive"))
    )
    (net (code "215") (name "unconnected-(U8-PA10-Pad31)") (class "Default")
      (node (ref "U8") (pin "31") (pinfunction "PA10_31") (pintype "passive"))
    )
    (net (code "216") (name "unconnected-(U8-PB0-Pad18)") (class "Default")
      (node (ref "U8") (pin "18") (pinfunction "PB0_18") (pintype "passive"))
    )
    (net (code "217") (name "unconnected-(U8-PB1-Pad19)") (class "Default")
      (node (ref "U8") (pin "19") (pinfunction "PB1_19") (pintype "passive"))
    )
    (net (code "218") (name "unconnected-(U8-PB2-Pad20)") (class "Default")
      (node (ref "U8") (pin "20") (pinfunction "PB2_20") (pintype "passive"))
    )
    (net (code "219") (name "unconnected-(U8-PB6-Pad42)") (class "Default")
      (node (ref "U8") (pin "42") (pinfunction "PB6_42") (pintype "passive"))
    )
    (net (code "220") (name "unconnected-(U8-PB7-Pad43)") (class "Default")
      (node (ref "U8") (pin "43") (pinfunction "PB7_43") (pintype "passive"))
    )
    (net (code "221") (name "unconnected-(U8-PB8-Pad45)") (class "Default")
      (node (ref "U8") (pin "45") (pinfunction "PB8_45") (pintype "passive"))
    )
    (net (code "222") (name "unconnected-(U8-PB9-Pad46)") (class "Default")
      (node (ref "U8") (pin "46") (pinfunction "PB9_46") (pintype "passive"))
    )
    (net (code "223") (name "unconnected-(U8-PB14-Pad27)") (class "Default")
      (node (ref "U8") (pin "27") (pinfunction "PB14_27") (pintype "passive"))
    )
    (net (code "224") (name "unconnected-(U8-PB15-Pad28)") (class "Default")
      (node (ref "U8") (pin "28") (pinfunction "PB15_28") (pintype "passive"))
    )
    (net (code "225") (name "unconnected-(U8-PC13-Pad2)") (class "Default")
      (node (ref "U8") (pin "2") (pinfunction "PC13_2") (pintype "passive"))
    )
    (net (code "226") (name "unconnected-(U8-PC14-Pad3)") (class "Default")
      (node (ref "U8") (pin "3") (pinfunction "PC14_3") (pintype "passive"))
    )
    (net (code "227") (name "unconnected-(U8-PC15-Pad4)") (class "Default")
      (node (ref "U8") (pin "4") (pinfunction "PC15_4") (pintype "passive"))
    )
    (net (code "228") (name "unconnected-(U8-PD0-Pad5)") (class "Default")
      (node (ref "U8") (pin "5") (pinfunction "PD0_5") (pintype "passive"))
    )
    (net (code "229") (name "unconnected-(U8-PD1-Pad6)") (class "Default")
      (node (ref "U8") (pin "6") (pinfunction "PD1_6") (pintype "passive"))
    )
  )
)
